# CANTensegrityBoard.net
KiCad netlist of a schematic drawn in EAGLE
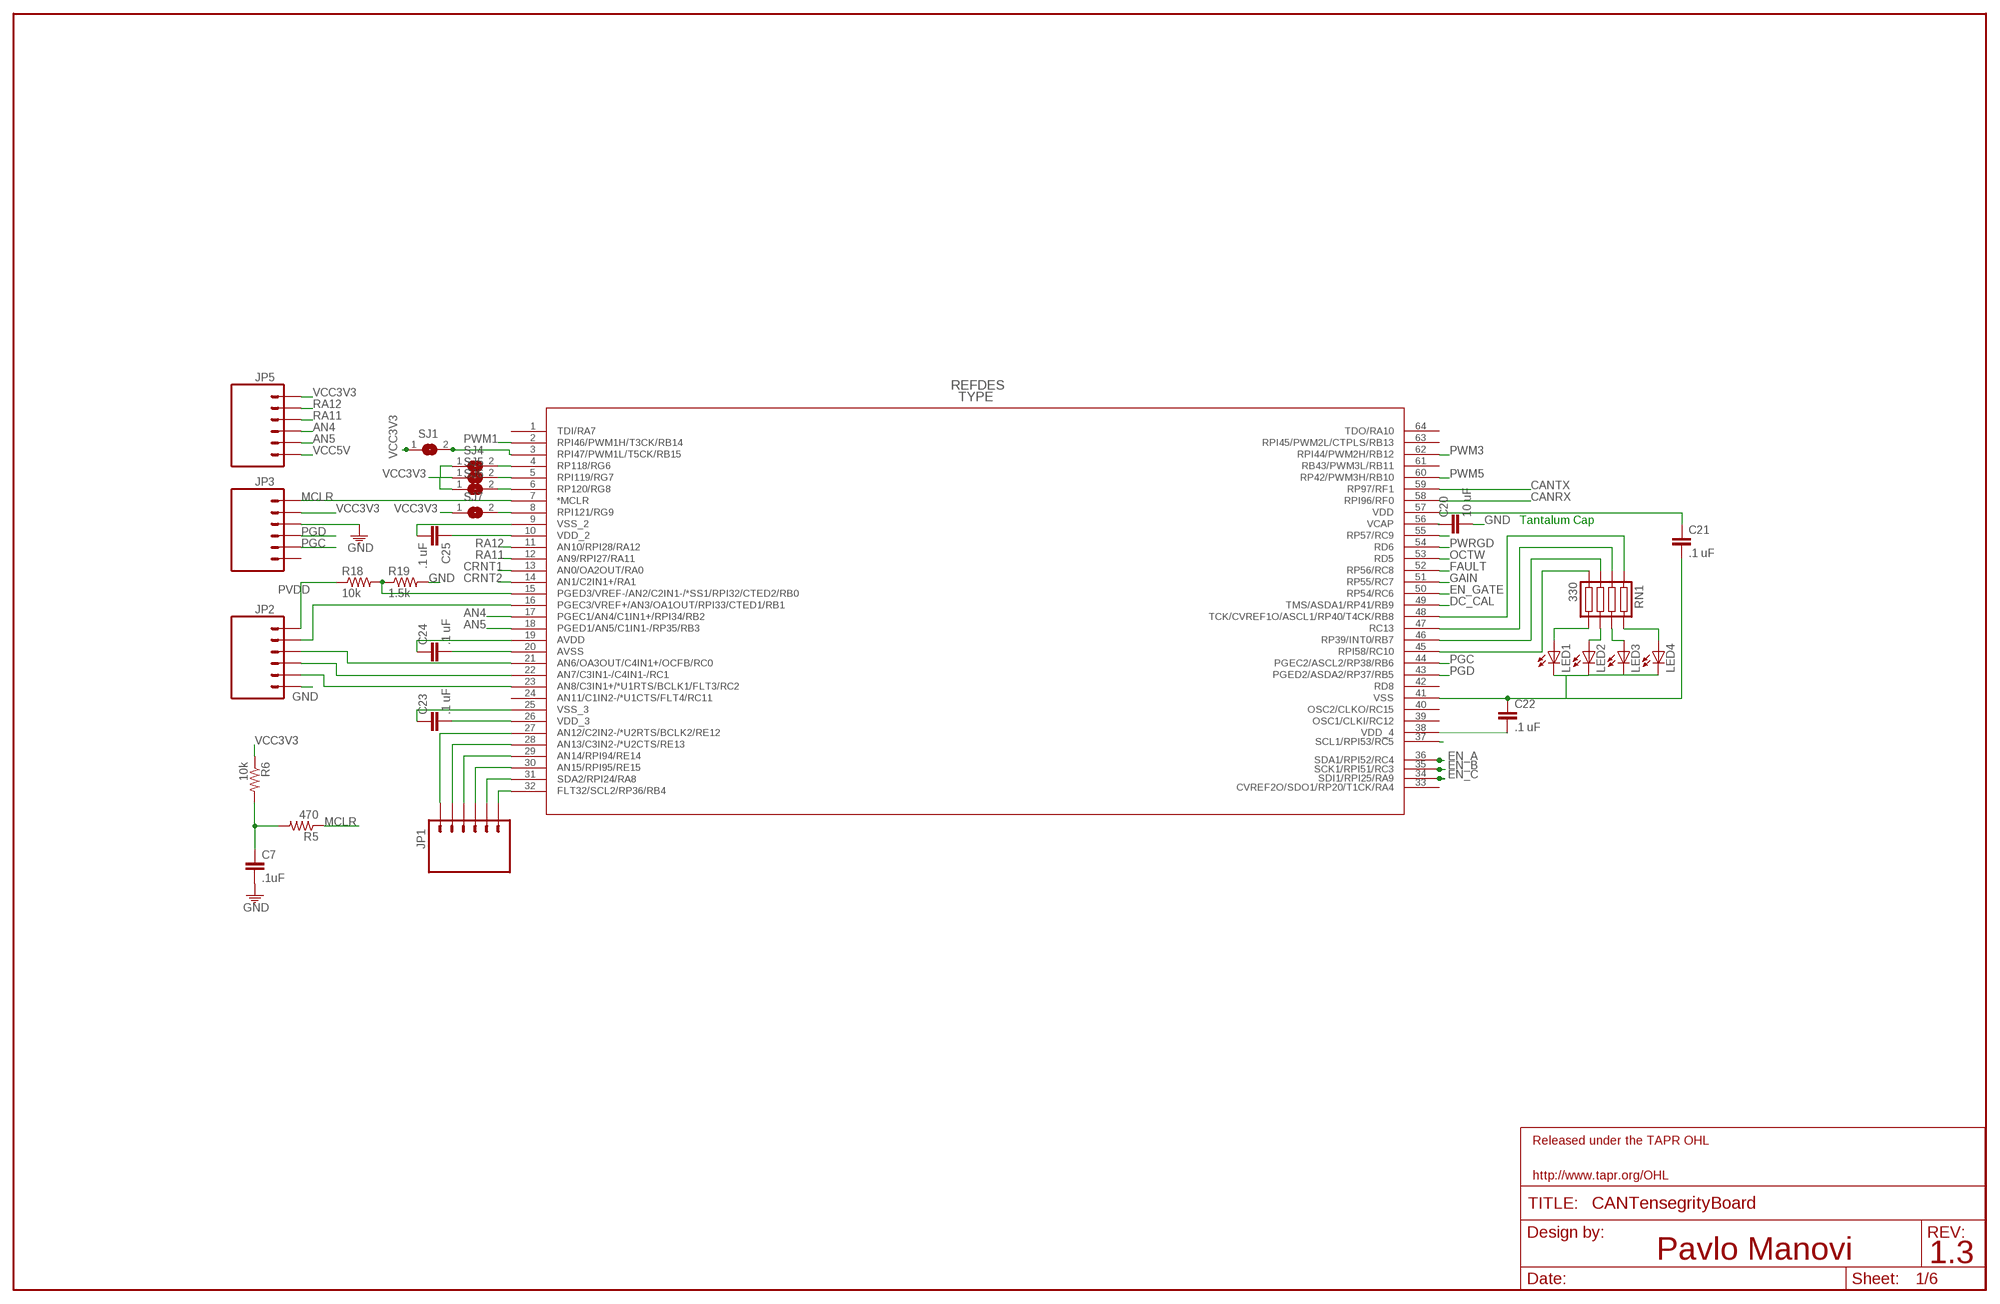
[diagram p0: schematic, sheet 1]
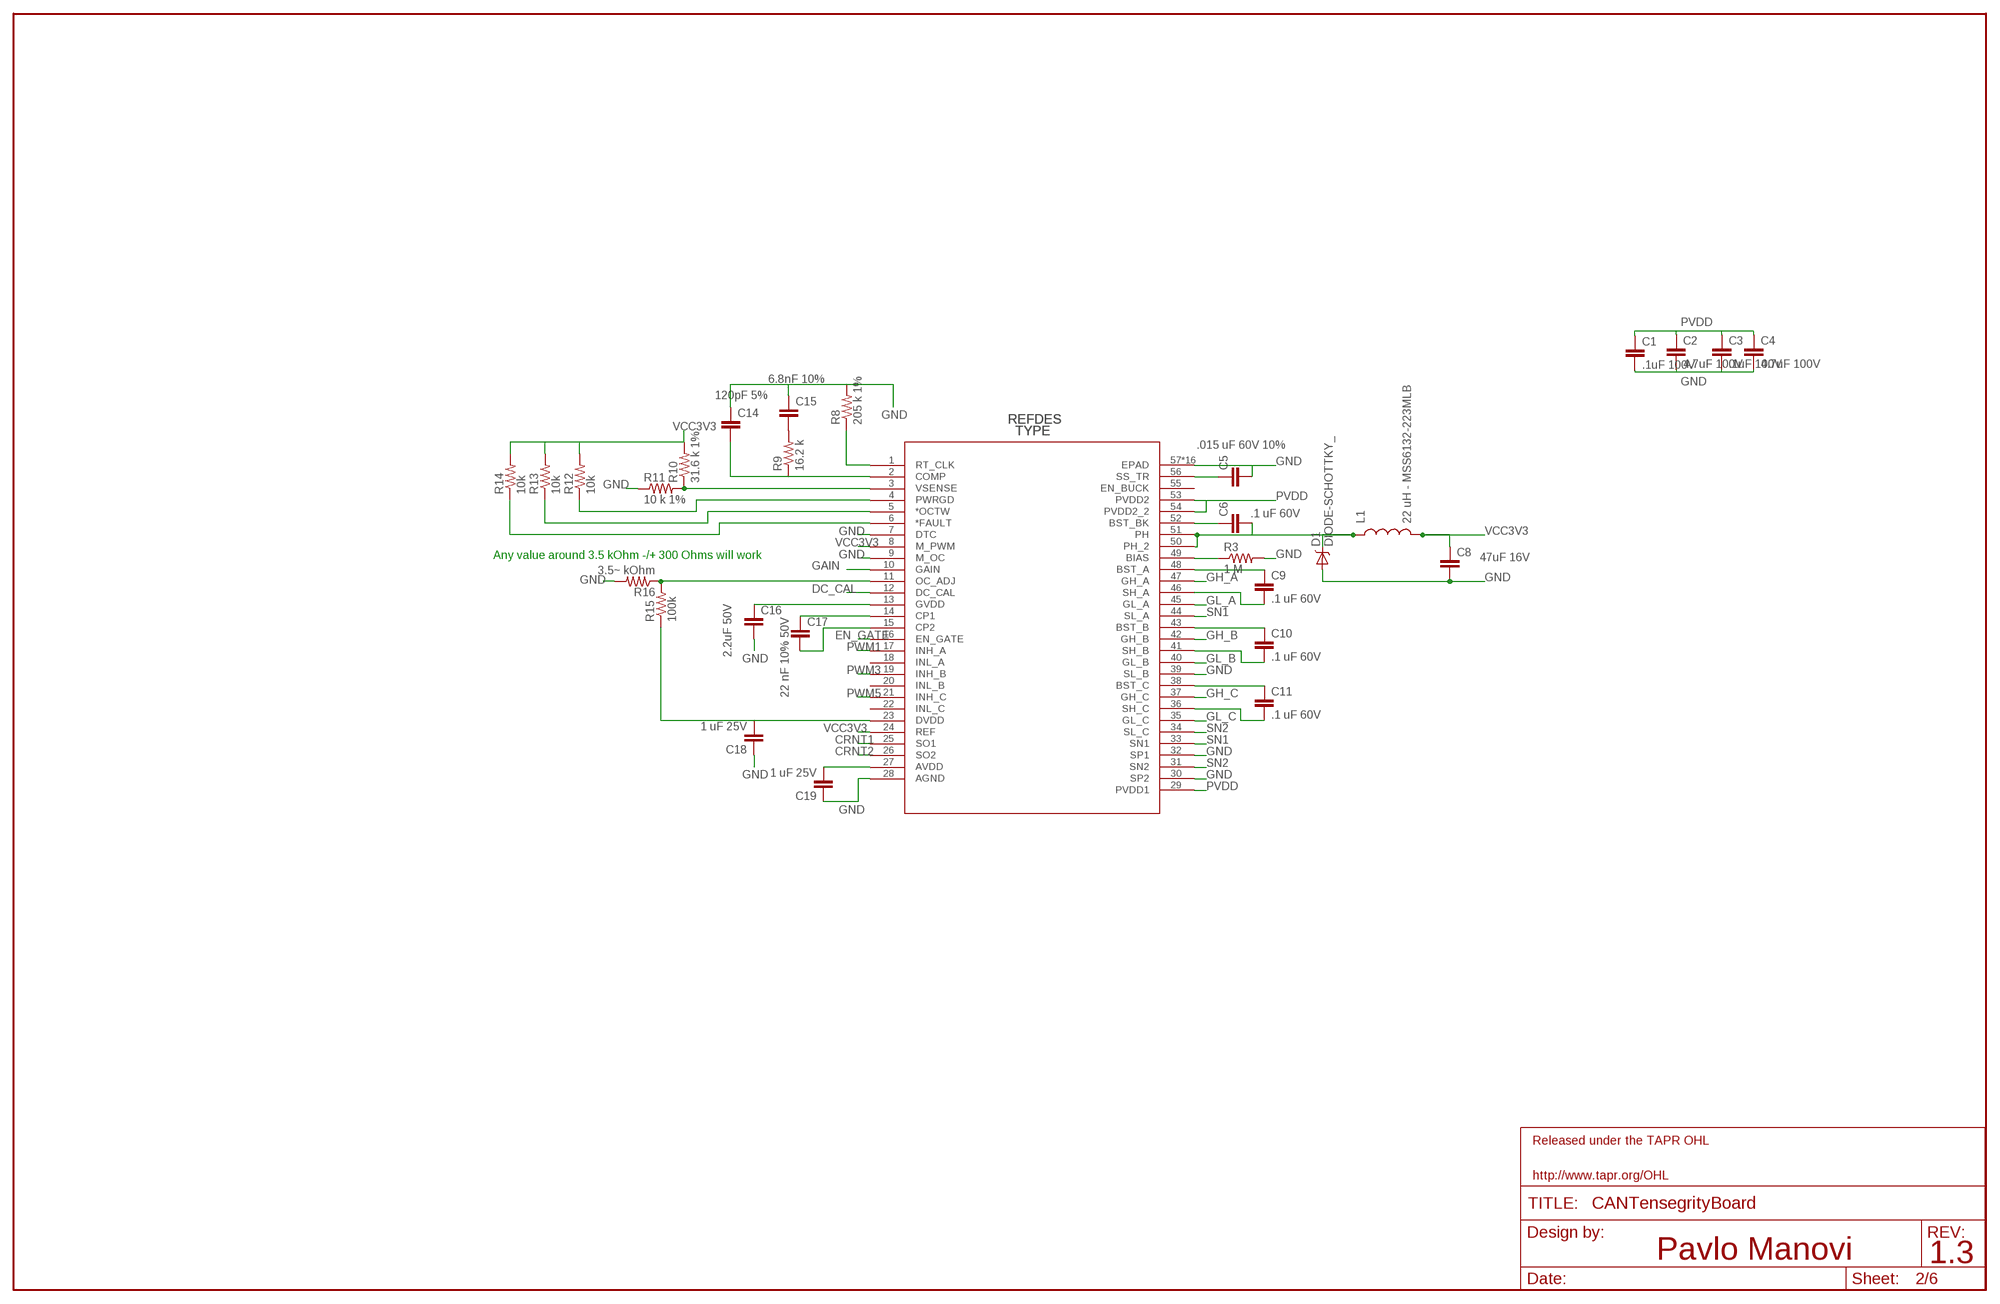
[diagram p1: schematic, sheet 2]
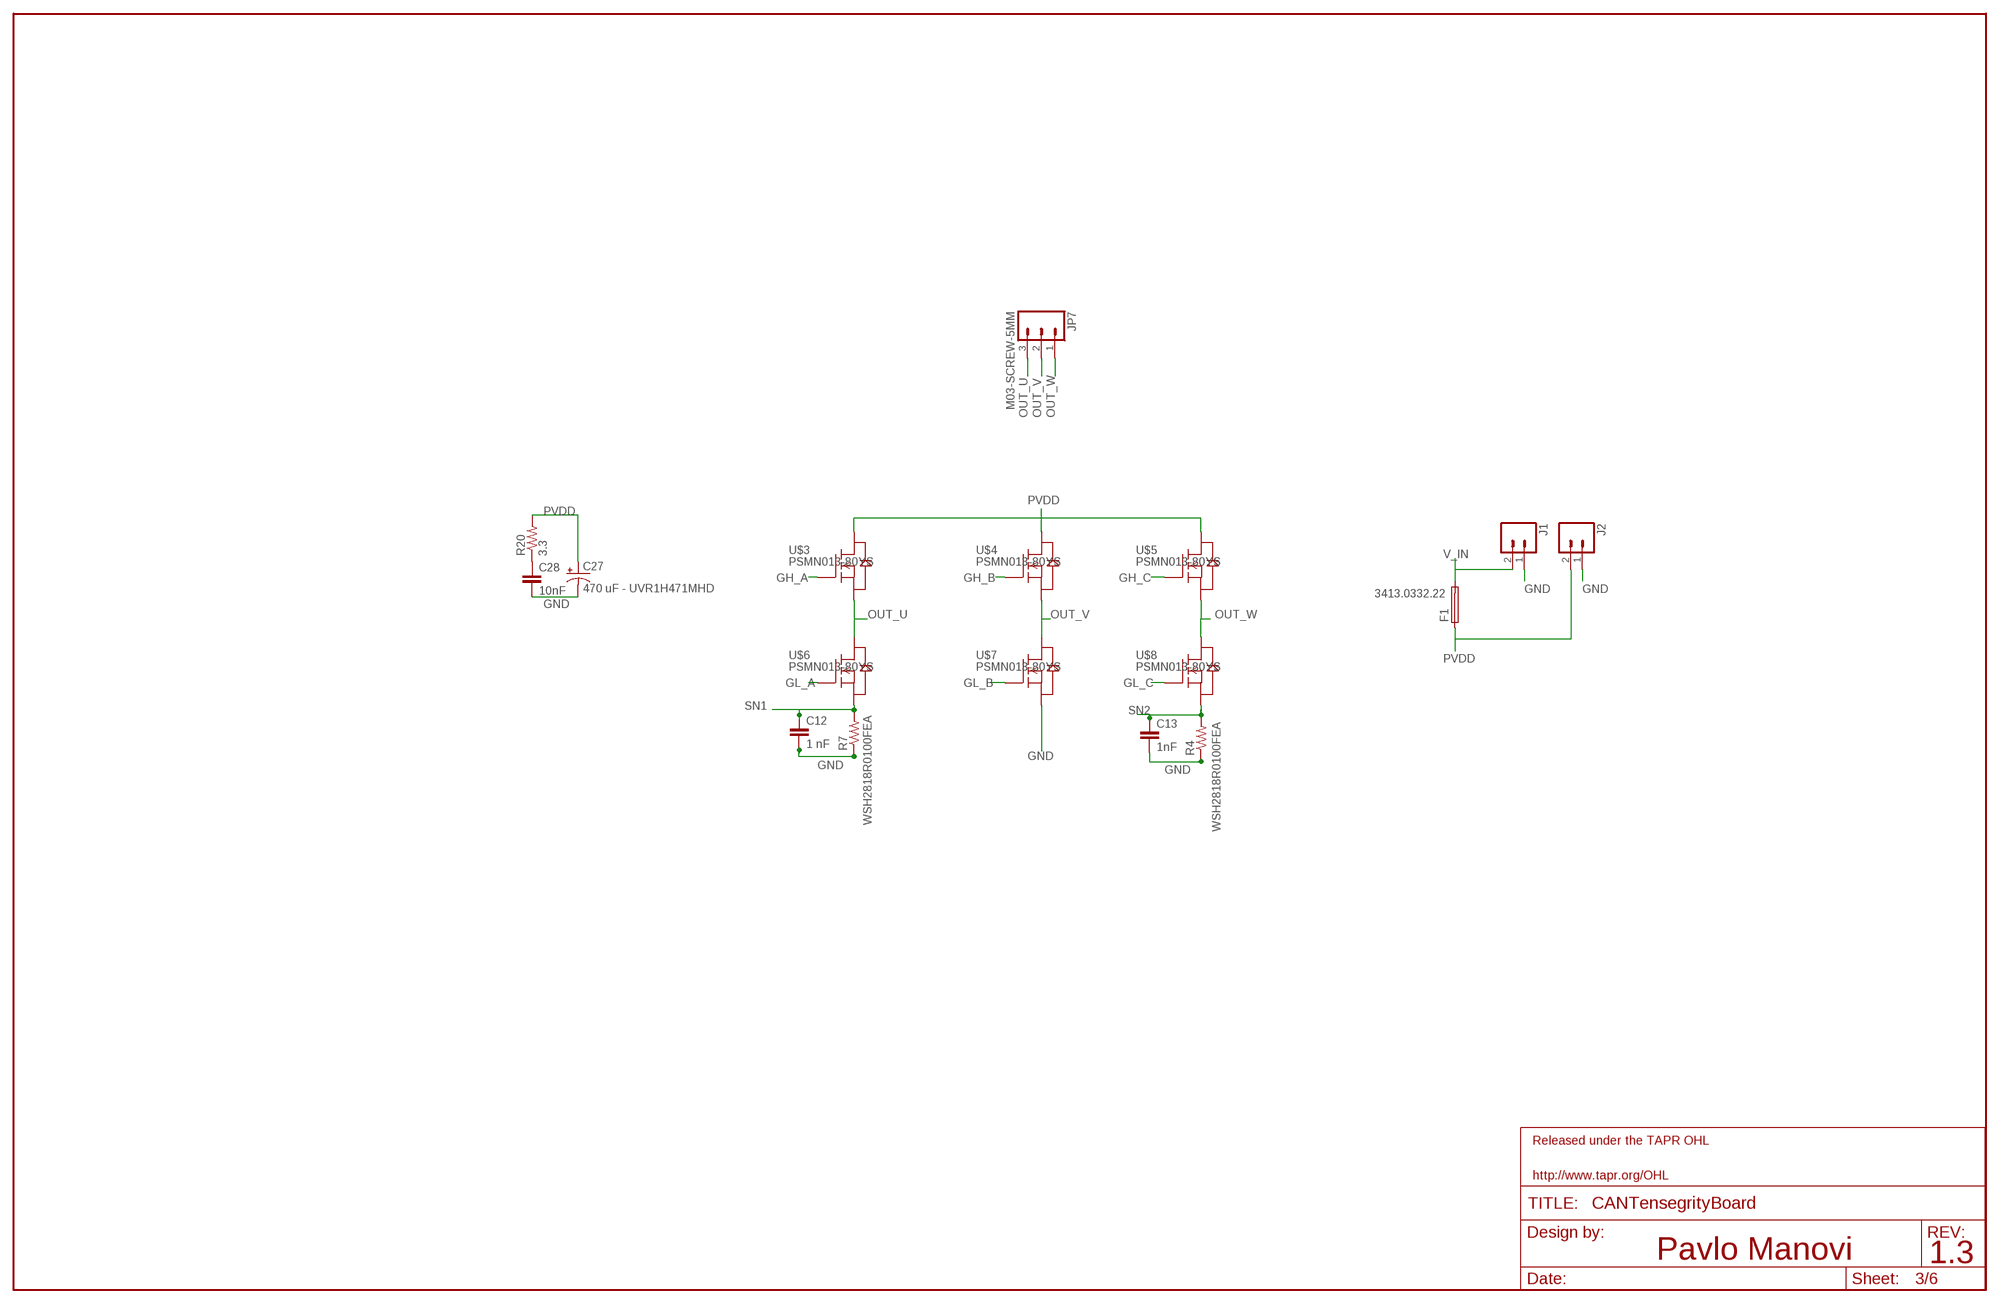
[diagram p2: schematic, sheet 3]
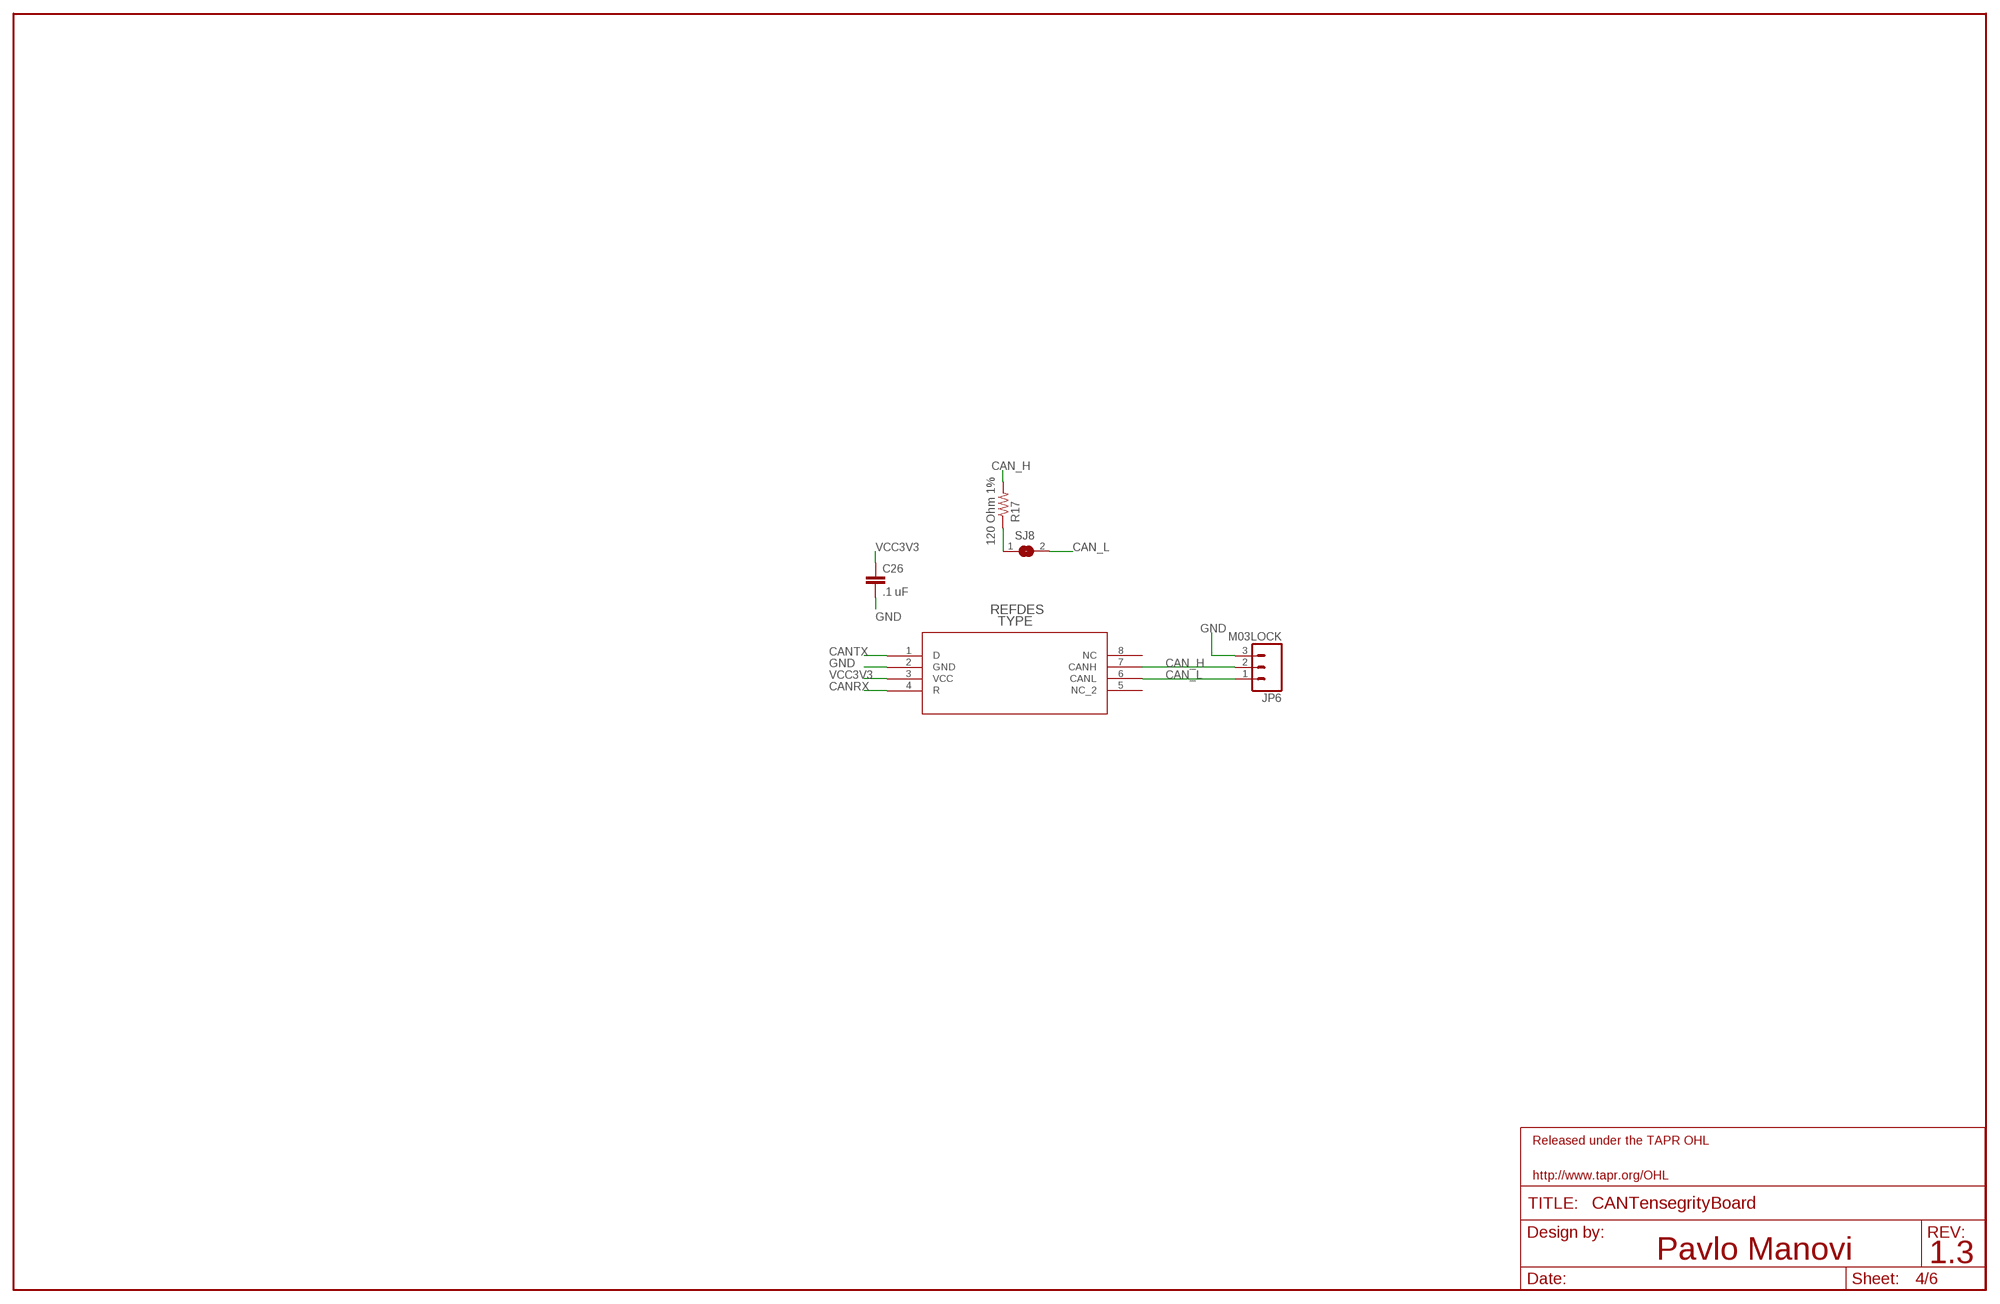
[diagram p3: schematic, sheet 4]
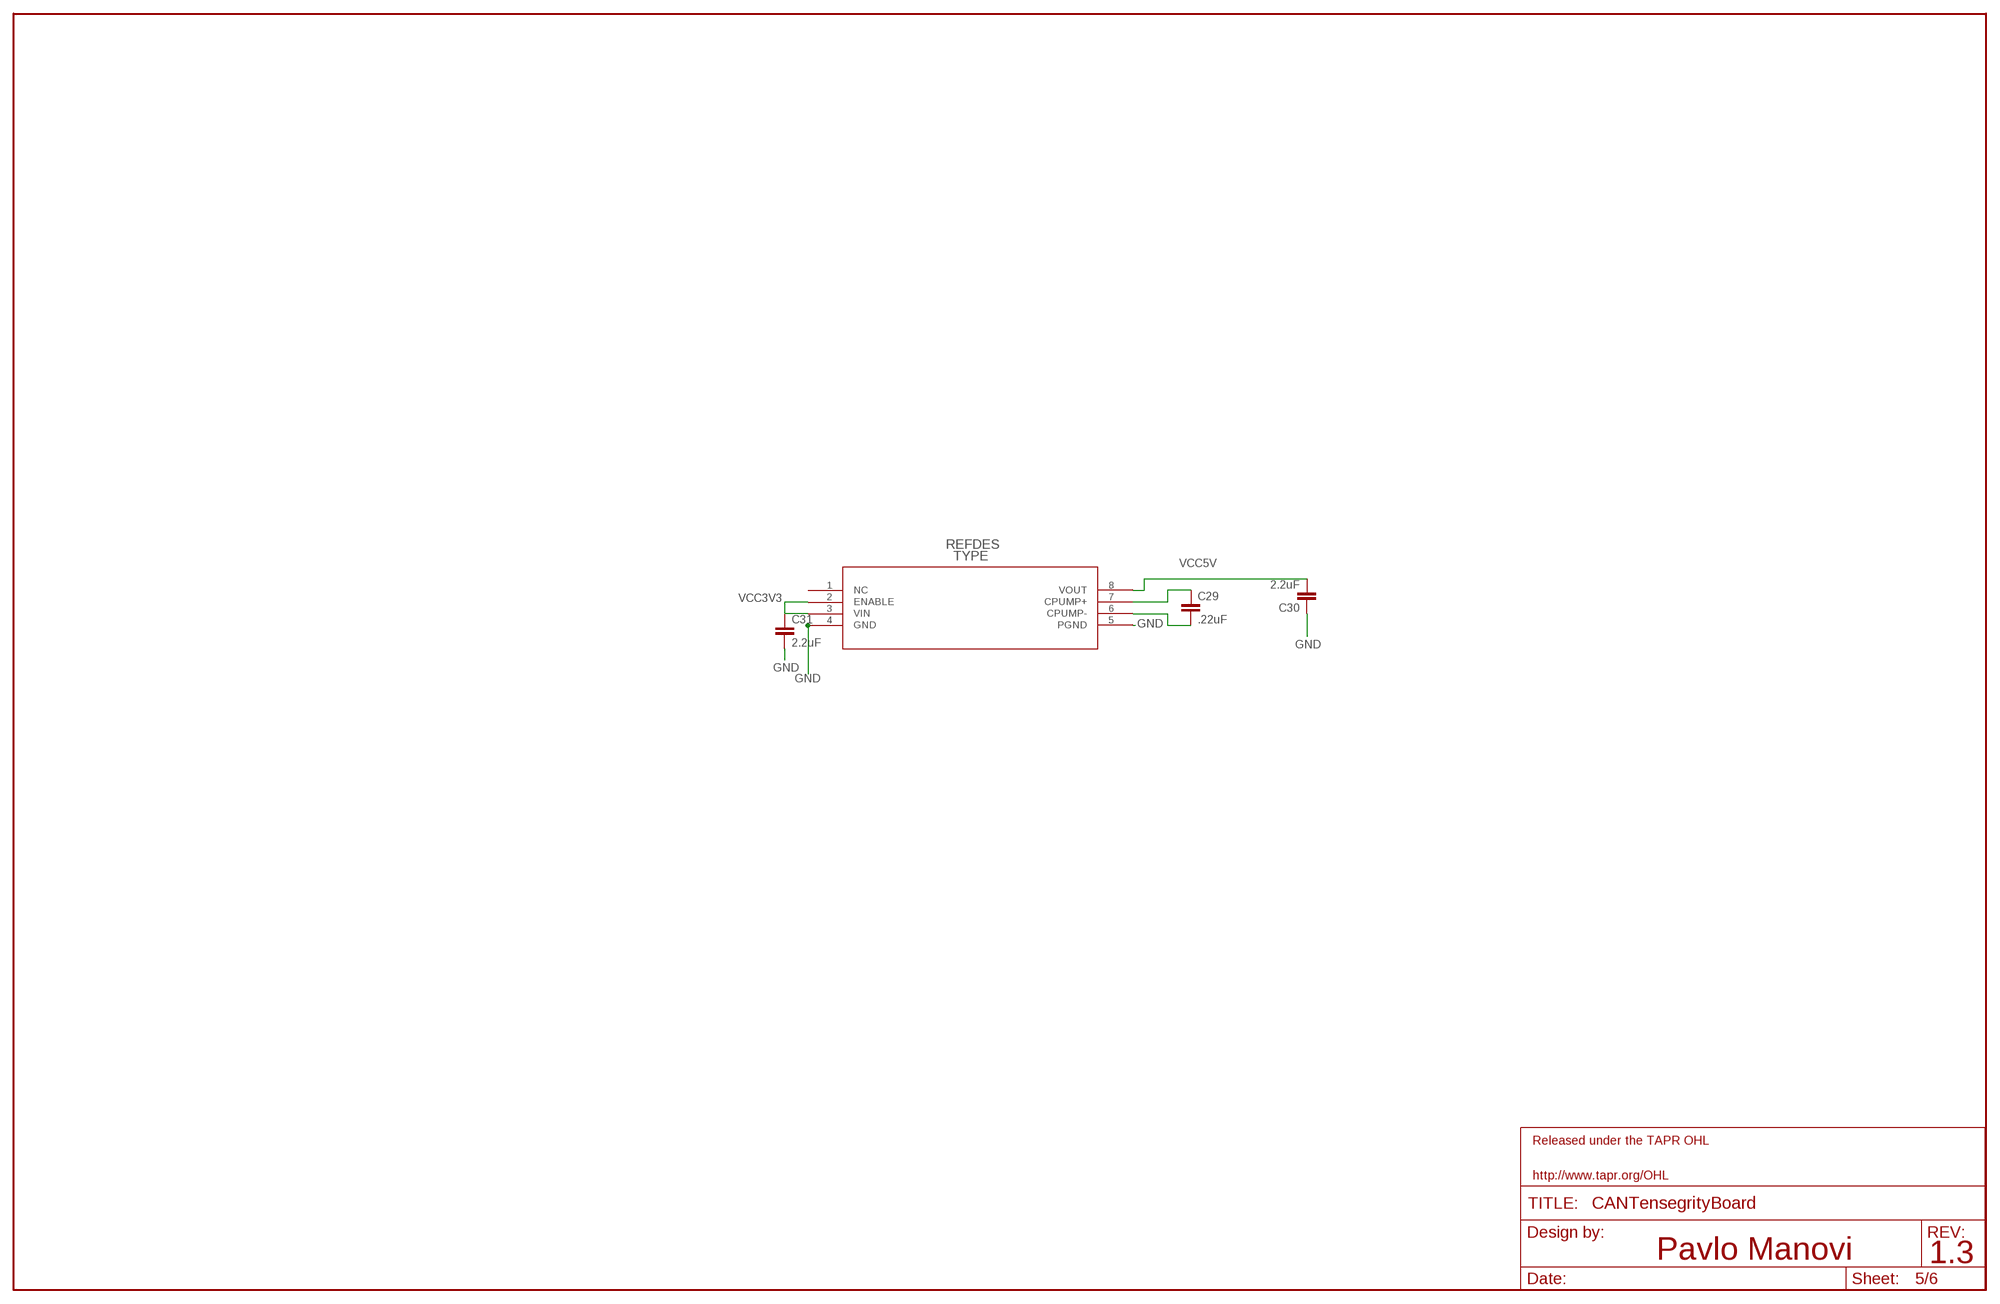
[diagram p4: schematic, sheet 5]
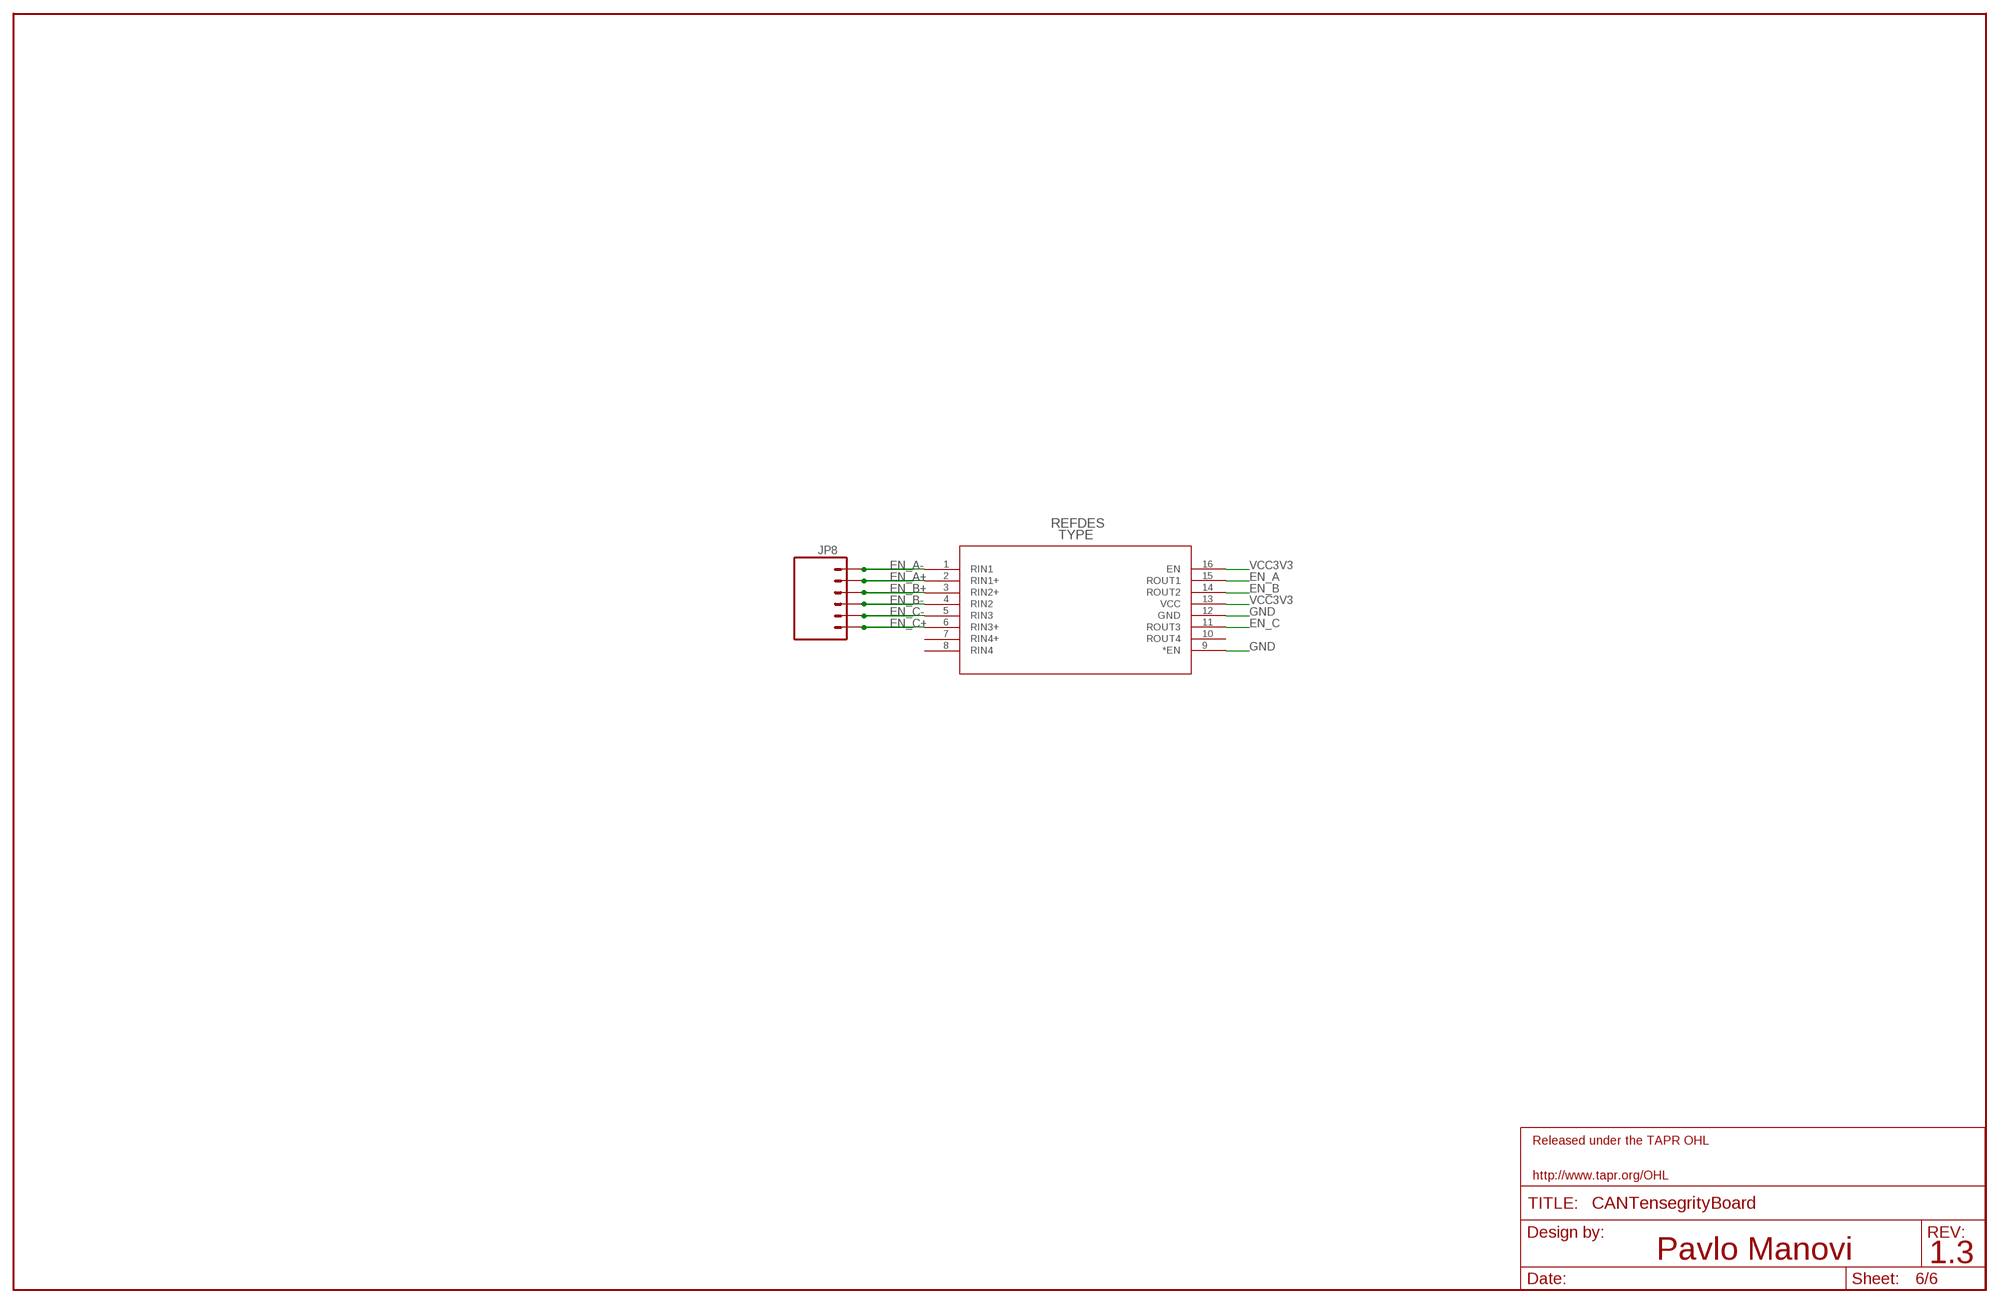
[diagram p5: schematic, sheet 6]

(export (version "E")
  (design (tool "Eeschema 10.0.6"))
  (components
    (comp (ref "C1")
      (value ".1uF 100V")
      (footprint "eagle-import:0805")
      (libsource (lib "eagle-import") (part "CAP0805"))
    )
    (comp (ref "C2")
      (value "4.7uF 100V")
      (footprint "eagle-import:1206")
      (libsource (lib "eagle-import") (part "CAP1206"))
    )
    (comp (ref "C3")
      (value ".1uF 100V")
      (footprint "eagle-import:0805")
      (libsource (lib "eagle-import") (part "CAP0805"))
    )
    (comp (ref "C4")
      (value "4.7uF 100V")
      (footprint "eagle-import:1206")
      (libsource (lib "eagle-import") (part "CAP1206"))
    )
    (comp (ref "C5")
      (value ".015 uF 60V 10%")
      (footprint "eagle-import:0805")
      (libsource (lib "eagle-import") (part "CAP0805"))
    )
    (comp (ref "C6")
      (value ".1 uF 60V")
      (footprint "eagle-import:0805")
      (libsource (lib "eagle-import") (part "CAP0805"))
    )
    (comp (ref "C8")
      (value "47uF 16V")
      (footprint "eagle-import:1206")
      (libsource (lib "eagle-import") (part "CAP1206"))
    )
    (comp (ref "C9")
      (value ".1 uF 60V")
      (footprint "eagle-import:0805")
      (libsource (lib "eagle-import") (part "CAP0805"))
    )
    (comp (ref "C10")
      (value ".1 uF 60V")
      (footprint "eagle-import:0805")
      (libsource (lib "eagle-import") (part "CAP0805"))
    )
    (comp (ref "C11")
      (value ".1 uF 60V")
      (footprint "eagle-import:0805")
      (libsource (lib "eagle-import") (part "CAP0805"))
    )
    (comp (ref "C14")
      (value "120pF 5%")
      (footprint "eagle-import:0805")
      (libsource (lib "eagle-import") (part "CAP0805"))
    )
    (comp (ref "C15")
      (value "6.8nF 10%")
      (footprint "eagle-import:0805")
      (libsource (lib "eagle-import") (part "CAP0805"))
    )
    (comp (ref "C16")
      (value "2.2uF 50V")
      (footprint "eagle-import:1206")
      (libsource (lib "eagle-import") (part "CAP1206"))
    )
    (comp (ref "C17")
      (value "22 nF 10% 50V")
      (footprint "eagle-import:0805")
      (libsource (lib "eagle-import") (part "CAP0805"))
    )
    (comp (ref "C18")
      (value "1 uF 25V")
      (footprint "eagle-import:0805")
      (libsource (lib "eagle-import") (part "CAP0805"))
    )
    (comp (ref "C19")
      (value "1 uF 25V")
      (footprint "eagle-import:0805")
      (libsource (lib "eagle-import") (part "CAP0805"))
    )
    (comp (ref "D1")
      (value "DIODE-SCHOTTKY_")
      (footprint "eagle-import:SMA-DIODE")
      (libsource (lib "eagle-import") (part "DIODE-SCHOTTKY_"))
    )
    (comp (ref "L1")
      (value "22 uH - MSS6132-223MLB")
      (footprint "eagle-import:MSS6132")
      (libsource (lib "eagle-import") (part "INDUCTOR"))
    )
    (comp (ref "R3")
      (value "1 M")
      (footprint "eagle-import:0805")
      (libsource (lib "eagle-import") (part "RESISTOR0805-RES"))
    )
    (comp (ref "R8")
      (value "205 k 1%")
      (footprint "eagle-import:0805")
      (libsource (lib "eagle-import") (part "RESISTOR0805-RES"))
    )
    (comp (ref "R9")
      (value "16.2 k")
      (footprint "eagle-import:0805")
      (libsource (lib "eagle-import") (part "RESISTOR0805-RES"))
    )
    (comp (ref "R10")
      (value "31.6 k 1%")
      (footprint "eagle-import:0805")
      (libsource (lib "eagle-import") (part "RESISTOR0805-RES"))
    )
    (comp (ref "R11")
      (value "10 k 1%")
      (footprint "eagle-import:0805")
      (libsource (lib "eagle-import") (part "RESISTOR0805-RES"))
    )
    (comp (ref "R12")
      (value "10k")
      (footprint "eagle-import:0805")
      (libsource (lib "eagle-import") (part "RESISTOR0805-RES"))
    )
    (comp (ref "R13")
      (value "10k")
      (footprint "eagle-import:0805")
      (libsource (lib "eagle-import") (part "RESISTOR0805-RES"))
    )
    (comp (ref "R14")
      (value "10k")
      (footprint "eagle-import:0805")
      (libsource (lib "eagle-import") (part "RESISTOR0805-RES"))
    )
    (comp (ref "R15")
      (value "100k")
      (footprint "eagle-import:0805")
      (libsource (lib "eagle-import") (part "RESISTOR0805-RES"))
    )
    (comp (ref "R16")
      (value "3.5~ kOhm")
      (footprint "eagle-import:0805")
      (libsource (lib "eagle-import") (part "RESISTOR0805-RES"))
    )
    (comp (ref "U$2")
      (value "DRV8302")
      (footprint "eagle-import:DCA56_6P35X3P600")
      (libsource (lib "eagle-import") (part "DRV8302"))
    )
    (comp (ref "C12")
      (value "1 nF")
      (footprint "eagle-import:0805")
      (libsource (lib "eagle-import") (part "CAP0805"))
    )
    (comp (ref "C13")
      (value "1nF")
      (footprint "eagle-import:0805")
      (libsource (lib "eagle-import") (part "CAP0805"))
    )
    (comp (ref "C27")
      (value "470 uF - UVR1H471MHD")
      (footprint "eagle-import:CPOL-RADIAL-1000UF-25V")
      (libsource (lib "eagle-import") (part "CAP_POLPTH4"))
    )
    (comp (ref "C28")
      (value "10nF")
      (footprint "eagle-import:0805")
      (libsource (lib "eagle-import") (part "CAP0805"))
    )
    (comp (ref "F1")
      (value "3413.0332.22")
      (footprint "eagle-import:LED-1206")
      (libsource (lib "eagle-import") (part "TE5"))
    )
    (comp (ref "J1")
      (value "M02PTH4")
      (footprint "eagle-import:1X02_XTRA_BIG")
      (libsource (lib "eagle-import") (part "M02PTH4"))
    )
    (comp (ref "J2")
      (value "M02PTH4")
      (footprint "eagle-import:1X02_XTRA_BIG")
      (libsource (lib "eagle-import") (part "M02PTH4"))
    )
    (comp (ref "JP7")
      (value "M03-SCREW-5MM")
      (footprint "eagle-import:SCREWTERMINAL-5MM-3")
      (libsource (lib "eagle-import") (part "pavlo_M03-SCREW-5MM"))
    )
    (comp (ref "R4")
      (value "WSH2818R0100FEA")
      (footprint "eagle-import:SMT-REF")
      (libsource (lib "eagle-import") (part "RESISTOR"))
    )
    (comp (ref "R7")
      (value "WSH2818R0100FEA")
      (footprint "eagle-import:SMT-REF")
      (libsource (lib "eagle-import") (part "RESISTOR"))
    )
    (comp (ref "R20")
      (value "3.3")
      (footprint "eagle-import:0805")
      (libsource (lib "eagle-import") (part "RESISTOR0805-RES"))
    )
    (comp (ref "U$3")
      (value "PSMN013-80YS")
      (footprint "eagle-import:TO127P600X120-5N")
      (libsource (lib "eagle-import") (part "PSMN013-80YS"))
    )
    (comp (ref "U$4")
      (value "PSMN013-80YS")
      (footprint "eagle-import:TO127P600X120-5N")
      (libsource (lib "eagle-import") (part "PSMN013-80YS"))
    )
    (comp (ref "U$5")
      (value "PSMN013-80YS")
      (footprint "eagle-import:TO127P600X120-5N")
      (libsource (lib "eagle-import") (part "PSMN013-80YS"))
    )
    (comp (ref "U$6")
      (value "PSMN013-80YS")
      (footprint "eagle-import:TO127P600X120-5N")
      (libsource (lib "eagle-import") (part "PSMN013-80YS"))
    )
    (comp (ref "U$7")
      (value "PSMN013-80YS")
      (footprint "eagle-import:TO127P600X120-5N")
      (libsource (lib "eagle-import") (part "PSMN013-80YS"))
    )
    (comp (ref "U$8")
      (value "PSMN013-80YS")
      (footprint "eagle-import:TO127P600X120-5N")
      (libsource (lib "eagle-import") (part "PSMN013-80YS"))
    )
    (comp (ref "JP8")
      (value "M06SIP_LOCK")
      (footprint "eagle-import:1X06-SIP_LOCK")
      (libsource (lib "eagle-import") (part "M06SIP_LOCK"))
    )
    (comp (ref "U3")
      (value "SN65LVDT348_PW_1")
      (footprint "eagle-import:PW16")
      (libsource (lib "eagle-import") (part "SN65LVDT348_PW_1"))
    )
    (comp (ref "C29")
      (value ".22uF")
      (footprint "eagle-import:0805")
      (libsource (lib "eagle-import") (part "CAP0805"))
    )
    (comp (ref "C30")
      (value "2.2uF")
      (footprint "eagle-import:0805")
      (libsource (lib "eagle-import") (part "CAP0805"))
    )
    (comp (ref "C31")
      (value "2.2uF")
      (footprint "eagle-import:0805")
      (libsource (lib "eagle-import") (part "CAP0805"))
    )
    (comp (ref "U1")
      (value "REG711-5_DGK_8")
      (footprint "eagle-import:DGK8")
      (libsource (lib "eagle-import") (part "REG711-5_DGK_8"))
    )
    (comp (ref "C26")
      (value ".1 uF")
      (footprint "eagle-import:0805")
      (libsource (lib "eagle-import") (part "CAP0805"))
    )
    (comp (ref "JP6")
      (value "M03LOCK")
      (footprint "eagle-import:1X03_LOCK")
      (libsource (lib "eagle-import") (part "M03LOCK"))
    )
    (comp (ref "R17")
      (value "120 Ohm 1%")
      (footprint "eagle-import:0805")
      (libsource (lib "eagle-import") (part "RESISTOR0805-RES"))
    )
    (comp (ref "SJ8") (value "SJ") (footprint "eagle-import:SJ") (libsource (lib "eagle-import") (part "SJ")))
    (comp (ref "U2")
      (value "SN65HVD232_D_8")
      (footprint "eagle-import:D8")
      (libsource (lib "eagle-import") (part "SN65HVD232_D_8"))
    )
    (comp (ref "C7")
      (value ".1uF")
      (footprint "eagle-import:0805")
      (libsource (lib "eagle-import") (part "CAP0805"))
    )
    (comp (ref "C20")
      (value "10 uF")
      (footprint "eagle-import:1206")
      (libsource (lib "eagle-import") (part "CAP1206"))
    )
    (comp (ref "C21")
      (value ".1 uF")
      (footprint "eagle-import:0805")
      (libsource (lib "eagle-import") (part "CAP0805"))
    )
    (comp (ref "C22")
      (value ".1 uF")
      (footprint "eagle-import:0805")
      (libsource (lib "eagle-import") (part "CAP0805"))
    )
    (comp (ref "C23")
      (value ".1 uF")
      (footprint "eagle-import:0805")
      (libsource (lib "eagle-import") (part "CAP0805"))
    )
    (comp (ref "C24")
      (value ".1 uF")
      (footprint "eagle-import:0805")
      (libsource (lib "eagle-import") (part "CAP0805"))
    )
    (comp (ref "C25")
      (value ".1 uF")
      (footprint "eagle-import:0805")
      (libsource (lib "eagle-import") (part "CAP0805"))
    )
    (comp (ref "JP1")
      (value "M06SIP")
      (footprint "eagle-import:1X06")
      (libsource (lib "eagle-import") (part "M06SIP"))
    )
    (comp (ref "JP2")
      (value "M06SIP")
      (footprint "eagle-import:1X06")
      (libsource (lib "eagle-import") (part "M06SIP"))
    )
    (comp (ref "JP3")
      (value "M06LOCK")
      (footprint "eagle-import:1X06_LOCK")
      (libsource (lib "eagle-import") (part "CMPE118lib_M06LOCK"))
    )
    (comp (ref "JP5")
      (value "M06LOCK")
      (footprint "eagle-import:1X06_LOCK")
      (libsource (lib "eagle-import") (part "CMPE118lib_M06LOCK"))
    )
    (comp (ref "LED1")
      (value "LED0805")
      (footprint "eagle-import:LED-0805")
      (libsource (lib "eagle-import") (part "LED0805"))
    )
    (comp (ref "LED2")
      (value "LED0805")
      (footprint "eagle-import:LED-0805")
      (libsource (lib "eagle-import") (part "LED0805"))
    )
    (comp (ref "LED3")
      (value "LED0805")
      (footprint "eagle-import:LED-0805")
      (libsource (lib "eagle-import") (part "LED0805"))
    )
    (comp (ref "LED4")
      (value "LED0805")
      (footprint "eagle-import:LED-0805")
      (libsource (lib "eagle-import") (part "LED0805"))
    )
    (comp (ref "R5")
      (value "470")
      (footprint "eagle-import:0805")
      (libsource (lib "eagle-import") (part "CMPE118lib_RESISTOR0805-RES"))
    )
    (comp (ref "R6")
      (value "10k")
      (footprint "eagle-import:0805")
      (libsource (lib "eagle-import") (part "CMPE118lib_RESISTOR0805-RES"))
    )
    (comp (ref "R18")
      (value "10k")
      (footprint "eagle-import:0805")
      (libsource (lib "eagle-import") (part "RESISTOR0805-RES"))
    )
    (comp (ref "R19")
      (value "1.5k")
      (footprint "eagle-import:0805")
      (libsource (lib "eagle-import") (part "RESISTOR0805-RES"))
    )
    (comp (ref "RN1")
      (value "330")
      (footprint "eagle-import:EXB-38V271JV")
      (libsource (lib "eagle-import") (part "RESISTOR_ARRAY-4"))
    )
    (comp (ref "SJ1") (value "SJ") (footprint "eagle-import:SJ") (libsource (lib "eagle-import") (part "SJ")))
    (comp (ref "SJ4") (value "SJ") (footprint "eagle-import:SJ") (libsource (lib "eagle-import") (part "SJ")))
    (comp (ref "SJ5") (value "SJ") (footprint "eagle-import:SJ") (libsource (lib "eagle-import") (part "SJ")))
    (comp (ref "SJ6") (value "SJ") (footprint "eagle-import:SJ") (libsource (lib "eagle-import") (part "SJ")))
    (comp (ref "SJ7") (value "SJ") (footprint "eagle-import:SJ") (libsource (lib "eagle-import") (part "SJ")))
    (comp (ref "U$1")
      (value "DSPIC33EP128MC502-I/SS")
      (footprint "eagle-import:QFP64-10X10MC")
      (libsource (lib "eagle-import") (part "DSPIC33EP256MC50"))
    )
  )
  (nets
    (net (code "1") (name "AN4") (class "Default")
      (node (ref "JP5") (pin "4") (pinfunction "4_4") (pintype "passive"))
      (node (ref "U$1") (pin "17") (pinfunction "PGEC1/AN4/C1IN1+/RPI34/RB2_17") (pintype "passive"))
    )
    (net (code "2") (name "AN5") (class "Default")
      (node (ref "JP5") (pin "5") (pinfunction "5_5") (pintype "passive"))
      (node (ref "U$1") (pin "18") (pinfunction "PGED1/AN5/C1IN1-/RP35/RB3_18") (pintype "passive"))
    )
    (net (code "3") (name "CANRX") (class "Default")
      (node (ref "U$1") (pin "58") (pinfunction "RPI96/RF0_58") (pintype "passive"))
      (node (ref "U2") (pin "4") (pinfunction "R_4") (pintype "passive"))
    )
    (net (code "4") (name "CANTX") (class "Default")
      (node (ref "U$1") (pin "59") (pinfunction "RP97/RF1_59") (pintype "passive"))
      (node (ref "U2") (pin "1") (pinfunction "D_1") (pintype "passive"))
    )
    (net (code "5") (name "CAN_H") (class "Default")
      (node (ref "JP6") (pin "2") (pinfunction "2_2") (pintype "passive"))
      (node (ref "R17") (pin "2") (pinfunction "2_2") (pintype "passive"))
      (node (ref "U2") (pin "7") (pinfunction "CANH_7") (pintype "passive"))
    )
    (net (code "6") (name "CAN_L") (class "Default")
      (node (ref "JP6") (pin "1") (pinfunction "1_1") (pintype "passive"))
      (node (ref "SJ8") (pin "2") (pinfunction "2_2") (pintype "passive"))
      (node (ref "U2") (pin "6") (pinfunction "CANL_6") (pintype "passive"))
    )
    (net (code "7") (name "CRNT1") (class "Default")
      (node (ref "U$1") (pin "13") (pinfunction "AN0/OA2OUT/RA0_13") (pintype "passive"))
      (node (ref "U$2") (pin "25") (pinfunction "SO1_25") (pintype "passive"))
    )
    (net (code "8") (name "CRNT2") (class "Default")
      (node (ref "U$1") (pin "14") (pinfunction "AN1/C2IN1+/RA1_14") (pintype "passive"))
      (node (ref "U$2") (pin "26") (pinfunction "SO2_26") (pintype "passive"))
    )
    (net (code "9") (name "DC_CAL") (class "Default")
      (node (ref "U$1") (pin "49") (pinfunction "TMS/ASDA1/RP41/RB9_49") (pintype "passive"))
      (node (ref "U$2") (pin "12") (pinfunction "DC_CAL_12") (pintype "passive"))
    )
    (net (code "10") (name "EN_A") (class "Default")
      (node (ref "U$1") (pin "36") (pinfunction "SDA1/RPI52/RC4_36") (pintype "passive"))
      (node (ref "U3") (pin "15") (pinfunction "ROUT1_15") (pintype "passive"))
    )
    (net (code "11") (name "EN_A+") (class "Default")
      (node (ref "JP8") (pin "2") (pinfunction "2_2") (pintype "passive"))
      (node (ref "U3") (pin "2") (pinfunction "RIN1+_2") (pintype "passive"))
    )
    (net (code "12") (name "EN_A-") (class "Default")
      (node (ref "JP8") (pin "1") (pinfunction "1_1") (pintype "passive"))
      (node (ref "U3") (pin "1") (pinfunction "RIN1_1") (pintype "passive"))
    )
    (net (code "13") (name "EN_B") (class "Default")
      (node (ref "U$1") (pin "35") (pinfunction "SCK1/RPI51/RC3_35") (pintype "passive"))
      (node (ref "U3") (pin "14") (pinfunction "ROUT2_14") (pintype "passive"))
    )
    (net (code "14") (name "EN_B+") (class "Default")
      (node (ref "JP8") (pin "3") (pinfunction "3_3") (pintype "passive"))
      (node (ref "U3") (pin "3") (pinfunction "RIN2+_3") (pintype "passive"))
    )
    (net (code "15") (name "EN_B-") (class "Default")
      (node (ref "JP8") (pin "4") (pinfunction "4_4") (pintype "passive"))
      (node (ref "U3") (pin "4") (pinfunction "RIN2_4") (pintype "passive"))
    )
    (net (code "16") (name "EN_C") (class "Default")
      (node (ref "U$1") (pin "34") (pinfunction "SDI1/RPI25/RA9_34") (pintype "passive"))
      (node (ref "U3") (pin "11") (pinfunction "ROUT3_11") (pintype "passive"))
    )
    (net (code "17") (name "EN_C+") (class "Default")
      (node (ref "JP8") (pin "6") (pinfunction "6_6") (pintype "passive"))
      (node (ref "U3") (pin "6") (pinfunction "RIN3+_6") (pintype "passive"))
    )
    (net (code "18") (name "EN_C-") (class "Default")
      (node (ref "JP8") (pin "5") (pinfunction "5_5") (pintype "passive"))
      (node (ref "U3") (pin "5") (pinfunction "RIN3_5") (pintype "passive"))
    )
    (net (code "19") (name "EN_GATE") (class "Default")
      (node (ref "U$1") (pin "50") (pinfunction "RP54/RC6_50") (pintype "passive"))
      (node (ref "U$2") (pin "16") (pinfunction "EN_GATE_16") (pintype "passive"))
    )
    (net (code "20") (name "FAULT") (class "Default")
      (node (ref "R14") (pin "1") (pinfunction "1_1") (pintype "passive"))
      (node (ref "U$1") (pin "52") (pinfunction "RP56/RC8_52") (pintype "passive"))
      (node (ref "U$2") (pin "6") (pinfunction "*FAULT_6") (pintype "passive"))
    )
    (net (code "21") (name "GAIN") (class "Default")
      (node (ref "U$1") (pin "51") (pinfunction "RP55/RC7_51") (pintype "passive"))
      (node (ref "U$2") (pin "10") (pinfunction "GAIN_10") (pintype "passive"))
    )
    (net (code "22") (name "GH_A") (class "Default")
      (node (ref "U$2") (pin "47") (pinfunction "GH_A_47") (pintype "passive"))
      (node (ref "U$3") (pin "4") (pinfunction "G_4") (pintype "passive"))
    )
    (net (code "23") (name "GH_B") (class "Default")
      (node (ref "U$2") (pin "42") (pinfunction "GH_B_42") (pintype "passive"))
      (node (ref "U$4") (pin "4") (pinfunction "G_4") (pintype "passive"))
    )
    (net (code "24") (name "GH_C") (class "Default")
      (node (ref "U$2") (pin "37") (pinfunction "GH_C_37") (pintype "passive"))
      (node (ref "U$5") (pin "4") (pinfunction "G_4") (pintype "passive"))
    )
    (net (code "25") (name "GL_A") (class "Default")
      (node (ref "U$2") (pin "45") (pinfunction "GL_A_45") (pintype "passive"))
      (node (ref "U$6") (pin "4") (pinfunction "G_4") (pintype "passive"))
    )
    (net (code "26") (name "GL_B") (class "Default")
      (node (ref "U$2") (pin "40") (pinfunction "GL_B_40") (pintype "passive"))
      (node (ref "U$7") (pin "4") (pinfunction "G_4") (pintype "passive"))
    )
    (net (code "27") (name "GL_C") (class "Default")
      (node (ref "U$2") (pin "35") (pinfunction "GL_C_35") (pintype "passive"))
      (node (ref "U$8") (pin "4") (pinfunction "G_4") (pintype "passive"))
    )
    (net (code "28") (name "GND") (class "Default")
      (node (ref "C1") (pin "2") (pinfunction "2_2") (pintype "passive"))
      (node (ref "C12") (pin "2") (pinfunction "2_2") (pintype "passive"))
      (node (ref "C13") (pin "2") (pinfunction "2_2") (pintype "passive"))
      (node (ref "C14") (pin "1") (pinfunction "1_1") (pintype "passive"))
      (node (ref "C15") (pin "1") (pinfunction "1_1") (pintype "passive"))
      (node (ref "C16") (pin "2") (pinfunction "2_2") (pintype "passive"))
      (node (ref "C18") (pin "1") (pinfunction "1_1") (pintype "passive"))
      (node (ref "C19") (pin "1") (pinfunction "1_1") (pintype "passive"))
      (node (ref "C2") (pin "2") (pinfunction "2_2") (pintype "passive"))
      (node (ref "C20") (pin "2") (pinfunction "2_2") (pintype "passive"))
      (node (ref "C21") (pin "2") (pinfunction "2_2") (pintype "passive"))
      (node (ref "C22") (pin "1") (pinfunction "1_1") (pintype "passive"))
      (node (ref "C23") (pin "1") (pinfunction "1_1") (pintype "passive"))
      (node (ref "C24") (pin "2") (pinfunction "2_2") (pintype "passive"))
      (node (ref "C25") (pin "2") (pinfunction "2_2") (pintype "passive"))
      (node (ref "C26") (pin "2") (pinfunction "2_2") (pintype "passive"))
      (node (ref "C27") (pin "2") (pinfunction "-_2") (pintype "passive"))
      (node (ref "C28") (pin "2") (pinfunction "2_2") (pintype "passive"))
      (node (ref "C3") (pin "2") (pinfunction "2_2") (pintype "passive"))
      (node (ref "C30") (pin "1") (pinfunction "1_1") (pintype "passive"))
      (node (ref "C31") (pin "2") (pinfunction "2_2") (pintype "passive"))
      (node (ref "C4") (pin "2") (pinfunction "2_2") (pintype "passive"))
      (node (ref "C5") (pin "2") (pinfunction "2_2") (pintype "passive"))
      (node (ref "C7") (pin "2") (pinfunction "2_2") (pintype "passive"))
      (node (ref "C8") (pin "2") (pinfunction "2_2") (pintype "passive"))
      (node (ref "D1") (pin "A") (pinfunction "A_A") (pintype "passive"))
      (node (ref "J1") (pin "1") (pinfunction "2_1") (pintype "passive"))
      (node (ref "J2") (pin "1") (pinfunction "2_1") (pintype "passive"))
      (node (ref "JP2") (pin "6") (pinfunction "6_6") (pintype "passive"))
      (node (ref "JP3") (pin "3") (pinfunction "3_3") (pintype "passive"))
      (node (ref "JP6") (pin "3") (pinfunction "3_3") (pintype "passive"))
      (node (ref "LED1") (pin "2") (pinfunction "C_2") (pintype "passive"))
      (node (ref "LED2") (pin "2") (pinfunction "C_2") (pintype "passive"))
      (node (ref "LED3") (pin "2") (pinfunction "C_2") (pintype "passive"))
      (node (ref "LED4") (pin "2") (pinfunction "C_2") (pintype "passive"))
      (node (ref "R11") (pin "1") (pinfunction "1_1") (pintype "passive"))
      (node (ref "R16") (pin "2") (pinfunction "2_2") (pintype "passive"))
      (node (ref "R19") (pin "2") (pinfunction "2_2") (pintype "passive"))
      (node (ref "R3") (pin "2") (pinfunction "2_2") (pintype "passive"))
      (node (ref "R4") (pin "1") (pinfunction "1_1") (pintype "passive"))
      (node (ref "R7") (pin "1") (pinfunction "1_1") (pintype "passive"))
      (node (ref "R8") (pin "2") (pinfunction "2_2") (pintype "passive"))
      (node (ref "U$1") (pin "20") (pinfunction "AVSS_20") (pintype "passive"))
      (node (ref "U$1") (pin "25") (pinfunction "VSS_3_25") (pintype "passive"))
      (node (ref "U$1") (pin "41") (pinfunction "VSS_41") (pintype "passive"))
      (node (ref "U$1") (pin "9") (pinfunction "VSS_2_9") (pintype "passive"))
      (node (ref "U$2") (pin "28") (pinfunction "AGND_28") (pintype "passive"))
      (node (ref "U$2") (pin "30") (pinfunction "SP2_30") (pintype "passive"))
      (node (ref "U$2") (pin "32") (pinfunction "SP1_32") (pintype "passive"))
      (node (ref "U$2") (pin "39") (pinfunction "SL_B_39") (pintype "passive"))
      (node (ref "U$2") (pin "57") (pinfunction "EPAD_57") (pintype "passive"))
      (node (ref "U$2") (pin "7") (pinfunction "DTC_7") (pintype "passive"))
      (node (ref "U$2") (pin "9") (pinfunction "M_OC_9") (pintype "passive"))
      (node (ref "U$2") (pin "P$1") (pinfunction "EPAD_P$1") (pintype "passive"))
      (node (ref "U$2") (pin "P$10") (pinfunction "EPAD_P$10") (pintype "passive"))
      (node (ref "U$2") (pin "P$11") (pinfunction "EPAD_P$11") (pintype "passive"))
      (node (ref "U$2") (pin "P$12") (pinfunction "EPAD_P$12") (pintype "passive"))
      (node (ref "U$2") (pin "P$13") (pinfunction "EPAD_P$13") (pintype "passive"))
      (node (ref "U$2") (pin "P$14") (pinfunction "EPAD_P$14") (pintype "passive"))
      (node (ref "U$2") (pin "P$15") (pinfunction "EPAD_P$15") (pintype "passive"))
      (node (ref "U$2") (pin "P$2") (pinfunction "EPAD_P$2") (pintype "passive"))
      (node (ref "U$2") (pin "P$3") (pinfunction "EPAD_P$3") (pintype "passive"))
      (node (ref "U$2") (pin "P$4") (pinfunction "EPAD_P$4") (pintype "passive"))
      (node (ref "U$2") (pin "P$5") (pinfunction "EPAD_P$5") (pintype "passive"))
      (node (ref "U$2") (pin "P$6") (pinfunction "EPAD_P$6") (pintype "passive"))
      (node (ref "U$2") (pin "P$7") (pinfunction "EPAD_P$7") (pintype "passive"))
      (node (ref "U$2") (pin "P$8") (pinfunction "EPAD_P$8") (pintype "passive"))
      (node (ref "U$2") (pin "P$9") (pinfunction "EPAD_P$9") (pintype "passive"))
      (node (ref "U$7") (pin "1") (pinfunction "S_1") (pintype "passive"))
      (node (ref "U$7") (pin "2") (pinfunction "S_2") (pintype "passive"))
      (node (ref "U$7") (pin "3") (pinfunction "S_3") (pintype "passive"))
      (node (ref "U1") (pin "4") (pinfunction "GND_4") (pintype "passive"))
      (node (ref "U1") (pin "5") (pinfunction "PGND_5") (pintype "passive"))
      (node (ref "U2") (pin "2") (pinfunction "GND_2") (pintype "passive"))
      (node (ref "U3") (pin "12") (pinfunction "GND_12") (pintype "passive"))
      (node (ref "U3") (pin "9") (pinfunction "*EN_9") (pintype "passive"))
    )
    (net (code "29") (name "MCLR") (class "Default")
      (node (ref "JP3") (pin "1") (pinfunction "1_1") (pintype "passive"))
      (node (ref "R5") (pin "1") (pinfunction "1_1") (pintype "passive"))
      (node (ref "U$1") (pin "7") (pinfunction "*MCLR_7") (pintype "passive"))
    )
    (net (code "30") (name "Net-(C7-Pad1)") (class "Default")
      (node (ref "C7") (pin "1") (pinfunction "1_1") (pintype "passive"))
      (node (ref "R5") (pin "2") (pinfunction "2_2") (pintype "passive"))
      (node (ref "R6") (pin "2") (pinfunction "2_2") (pintype "passive"))
    )
    (net (code "31") (name "Net-(C15-Pad2)") (class "Default")
      (node (ref "C15") (pin "2") (pinfunction "2_2") (pintype "passive"))
      (node (ref "R9") (pin "2") (pinfunction "2_2") (pintype "passive"))
    )
    (net (code "32") (name "Net-(C28-Pad1)") (class "Default")
      (node (ref "C28") (pin "1") (pinfunction "1_1") (pintype "passive"))
      (node (ref "R20") (pin "1") (pinfunction "1_1") (pintype "passive"))
    )
    (net (code "33") (name "Net-(L1-1)") (class "Default")
      (node (ref "C6") (pin "2") (pinfunction "2_2") (pintype "passive"))
      (node (ref "D1") (pin "C") (pinfunction "C_C") (pintype "passive"))
      (node (ref "L1") (pin "P$1") (pinfunction "1_P$1") (pintype "passive"))
      (node (ref "U$2") (pin "51") (pinfunction "PH_51") (pintype "passive"))
    )
    (net (code "34") (name "Net-(LED1-A)") (class "Default")
      (node (ref "LED1") (pin "1") (pinfunction "A_1") (pintype "passive"))
      (node (ref "RN1") (pin "P$5") (pinfunction "5_P$5") (pintype "passive"))
    )
    (net (code "35") (name "Net-(LED2-A)") (class "Default")
      (node (ref "LED2") (pin "1") (pinfunction "A_1") (pintype "passive"))
      (node (ref "RN1") (pin "P$6") (pinfunction "6_P$6") (pintype "passive"))
    )
    (net (code "36") (name "Net-(LED3-A)") (class "Default")
      (node (ref "LED3") (pin "1") (pinfunction "A_1") (pintype "passive"))
      (node (ref "RN1") (pin "P$7") (pinfunction "7_P$7") (pintype "passive"))
    )
    (net (code "37") (name "Net-(LED4-A)") (class "Default")
      (node (ref "LED4") (pin "1") (pinfunction "A_1") (pintype "passive"))
      (node (ref "RN1") (pin "P$8") (pinfunction "8_P$8") (pintype "passive"))
    )
    (net (code "38") (name "Net-(R17-Pad1)") (class "Default")
      (node (ref "R17") (pin "1") (pinfunction "1_1") (pintype "passive"))
      (node (ref "SJ8") (pin "1") (pinfunction "1_1") (pintype "passive"))
    )
    (net (code "39") (name "Net-(RN1-1)") (class "Default")
      (node (ref "RN1") (pin "P$1") (pinfunction "1_P$1") (pintype "passive"))
      (node (ref "U$1") (pin "48") (pinfunction "TCK/CVREF1O/ASCL1/RP40/T4CK/RB8_48") (pintype "passive"))
    )
    (net (code "40") (name "Net-(RN1-2)") (class "Default")
      (node (ref "RN1") (pin "P$2") (pinfunction "2_P$2") (pintype "passive"))
      (node (ref "U$1") (pin "47") (pinfunction "RC13_47") (pintype "passive"))
    )
    (net (code "41") (name "Net-(RN1-3)") (class "Default")
      (node (ref "RN1") (pin "P$3") (pinfunction "3_P$3") (pintype "passive"))
      (node (ref "U$1") (pin "46") (pinfunction "RP39/INT0/RB7_46") (pintype "passive"))
    )
    (net (code "42") (name "Net-(RN1-4)") (class "Default")
      (node (ref "RN1") (pin "P$4") (pinfunction "4_P$4") (pintype "passive"))
      (node (ref "U$1") (pin "45") (pinfunction "RPI58/RC10_45") (pintype "passive"))
    )
    (net (code "43") (name "Net-(U$1-AN6{slash}OA3OUT{slash}C4IN1+{slash}OCFB{slash}RC0)") (class "Default")
      (node (ref "JP2") (pin "3") (pinfunction "3_3") (pintype "passive"))
      (node (ref "U$1") (pin "21") (pinfunction "AN6/OA3OUT/C4IN1+/OCFB/RC0_21") (pintype "passive"))
    )
    (net (code "44") (name "Net-(U$1-AN7{slash}C3IN1-{slash}C4IN1-{slash}RC1)") (class "Default")
      (node (ref "JP2") (pin "4") (pinfunction "4_4") (pintype "passive"))
      (node (ref "U$1") (pin "22") (pinfunction "AN7/C3IN1-/C4IN1-/RC1_22") (pintype "passive"))
    )
    (net (code "45") (name "Net-(U$1-AN8{slash}C3IN1+{slash}*U1RTS{slash}BCLK1{slash}FLT3{slash}RC2)") (class "Default")
      (node (ref "JP2") (pin "5") (pinfunction "5_5") (pintype "passive"))
      (node (ref "U$1") (pin "23") (pinfunction "AN8/C3IN1+/*U1RTS/BCLK1/FLT3/RC2_23") (pintype "passive"))
    )
    (net (code "46") (name "Net-(U$1-AN12{slash}C2IN2-{slash}*U2RTS{slash}BCLK2{slash}RE12)") (class "Default")
      (node (ref "JP1") (pin "1") (pinfunction "1_1") (pintype "passive"))
      (node (ref "U$1") (pin "27") (pinfunction "AN12/C2IN2-/*U2RTS/BCLK2/RE12_27") (pintype "passive"))
    )
    (net (code "47") (name "Net-(U$1-AN13{slash}C3IN2-{slash}*U2CTS{slash}RE13)") (class "Default")
      (node (ref "JP1") (pin "2") (pinfunction "2_2") (pintype "passive"))
      (node (ref "U$1") (pin "28") (pinfunction "AN13/C3IN2-/*U2CTS/RE13_28") (pintype "passive"))
    )
    (net (code "48") (name "Net-(U$1-AN14{slash}RPI94{slash}RE14)") (class "Default")
      (node (ref "JP1") (pin "3") (pinfunction "3_3") (pintype "passive"))
      (node (ref "U$1") (pin "29") (pinfunction "AN14/RPI94/RE14_29") (pintype "passive"))
    )
    (net (code "49") (name "Net-(U$1-AN15{slash}RPI95{slash}RE15)") (class "Default")
      (node (ref "JP1") (pin "4") (pinfunction "4_4") (pintype "passive"))
      (node (ref "U$1") (pin "30") (pinfunction "AN15/RPI95/RE15_30") (pintype "passive"))
    )
    (net (code "50") (name "Net-(U$1-FLT32{slash}SCL2{slash}RP36{slash}RB4)") (class "Default")
      (node (ref "JP1") (pin "6") (pinfunction "6_6") (pintype "passive"))
      (node (ref "U$1") (pin "32") (pinfunction "FLT32/SCL2/RP36/RB4_32") (pintype "passive"))
    )
    (net (code "51") (name "Net-(U$1-PGEC3{slash}VREF+{slash}AN3{slash}OA1OUT{slash}RPI33{slash}CTED1{slash}RB1)") (class "Default")
      (node (ref "JP2") (pin "2") (pinfunction "2_2") (pintype "passive"))
      (node (ref "U$1") (pin "16") (pinfunction "PGEC3/VREF+/AN3/OA1OUT/RPI33/CTED1/RB1_16") (pintype "passive"))
    )
    (net (code "52") (name "Net-(U$1-PGED3{slash}VREF-{slash}AN2{slash}C2IN1-{slash}*SS1{slash}RPI32{slash}CTED2{slash}RB0)") (class "Default")
      (node (ref "R18") (pin "2") (pinfunction "2_2") (pintype "passive"))
      (node (ref "R19") (pin "1") (pinfunction "1_1") (pintype "passive"))
      (node (ref "U$1") (pin "15") (pinfunction "PGED3/VREF-/AN2/C2IN1-/*SS1/RPI32/CTED2/RB0_15") (pintype "passive"))
    )
    (net (code "53") (name "Net-(U$1-RP118{slash}RG6)") (class "Default")
      (node (ref "SJ4") (pin "2") (pinfunction "2_2") (pintype "passive"))
      (node (ref "U$1") (pin "4") (pinfunction "RP118/RG6_4") (pintype "passive"))
    )
    (net (code "54") (name "Net-(U$1-RP120{slash}RG8)") (class "Default")
      (node (ref "SJ6") (pin "2") (pinfunction "2_2") (pintype "passive"))
      (node (ref "U$1") (pin "6") (pinfunction "RP120/RG8_6") (pintype "passive"))
    )
    (net (code "55") (name "Net-(U$1-RPI47{slash}PWM1L{slash}T5CK{slash}RB15)") (class "Default")
      (node (ref "SJ1") (pin "2") (pinfunction "2_2") (pintype "passive"))
      (node (ref "U$1") (pin "3") (pinfunction "RPI47/PWM1L/T5CK/RB15_3") (pintype "passive"))
    )
    (net (code "56") (name "Net-(U$1-RPI119{slash}RG7)") (class "Default")
      (node (ref "SJ5") (pin "2") (pinfunction "2_2") (pintype "passive"))
      (node (ref "U$1") (pin "5") (pinfunction "RPI119/RG7_5") (pintype "passive"))
    )
    (net (code "57") (name "Net-(U$1-RPI121{slash}RG9)") (class "Default")
      (node (ref "SJ7") (pin "2") (pinfunction "2_2") (pintype "passive"))
      (node (ref "U$1") (pin "8") (pinfunction "RPI121/RG9_8") (pintype "passive"))
    )
    (net (code "58") (name "Net-(U$1-SDA2{slash}RPI24{slash}RA8)") (class "Default")
      (node (ref "JP1") (pin "5") (pinfunction "5_5") (pintype "passive"))
      (node (ref "U$1") (pin "31") (pinfunction "SDA2/RPI24/RA8_31") (pintype "passive"))
    )
    (net (code "59") (name "Net-(U$1-VCAP)") (class "Default")
      (node (ref "C20") (pin "1") (pinfunction "1_1") (pintype "passive"))
      (node (ref "U$1") (pin "56") (pinfunction "VCAP_56") (pintype "passive"))
    )
    (net (code "60") (name "Net-(U$2-AVDD)") (class "Default")
      (node (ref "C19") (pin "2") (pinfunction "2_2") (pintype "passive"))
      (node (ref "U$2") (pin "27") (pinfunction "AVDD_27") (pintype "passive"))
    )
    (net (code "61") (name "Net-(U$2-BIAS)") (class "Default")
      (node (ref "R3") (pin "1") (pinfunction "1_1") (pintype "passive"))
      (node (ref "U$2") (pin "49") (pinfunction "BIAS_49") (pintype "passive"))
    )
    (net (code "62") (name "Net-(U$2-BST_A)") (class "Default")
      (node (ref "C9") (pin "1") (pinfunction "1_1") (pintype "passive"))
      (node (ref "U$2") (pin "48") (pinfunction "BST_A_48") (pintype "passive"))
    )
    (net (code "63") (name "Net-(U$2-BST_B)") (class "Default")
      (node (ref "C10") (pin "1") (pinfunction "1_1") (pintype "passive"))
      (node (ref "U$2") (pin "43") (pinfunction "BST_B_43") (pintype "passive"))
    )
    (net (code "64") (name "Net-(U$2-BST_BK)") (class "Default")
      (node (ref "C6") (pin "1") (pinfunction "1_1") (pintype "passive"))
      (node (ref "U$2") (pin "52") (pinfunction "BST_BK_52") (pintype "passive"))
    )
    (net (code "65") (name "Net-(U$2-BST_C)") (class "Default")
      (node (ref "C11") (pin "1") (pinfunction "1_1") (pintype "passive"))
      (node (ref "U$2") (pin "38") (pinfunction "BST_C_38") (pintype "passive"))
    )
    (net (code "66") (name "Net-(U$2-COMP)") (class "Default")
      (node (ref "C14") (pin "2") (pinfunction "2_2") (pintype "passive"))
      (node (ref "R9") (pin "1") (pinfunction "1_1") (pintype "passive"))
      (node (ref "U$2") (pin "2") (pinfunction "COMP_2") (pintype "passive"))
    )
    (net (code "67") (name "Net-(U$2-CP1)") (class "Default")
      (node (ref "C17") (pin "1") (pinfunction "1_1") (pintype "passive"))
      (node (ref "U$2") (pin "14") (pinfunction "CP1_14") (pintype "passive"))
    )
    (net (code "68") (name "Net-(U$2-CP2)") (class "Default")
      (node (ref "C17") (pin "2") (pinfunction "2_2") (pintype "passive"))
      (node (ref "U$2") (pin "15") (pinfunction "CP2_15") (pintype "passive"))
    )
    (net (code "69") (name "Net-(U$2-DVDD)") (class "Default")
      (node (ref "C18") (pin "2") (pinfunction "2_2") (pintype "passive"))
      (node (ref "R15") (pin "1") (pinfunction "1_1") (pintype "passive"))
      (node (ref "U$2") (pin "23") (pinfunction "DVDD_23") (pintype "passive"))
    )
    (net (code "70") (name "Net-(U$2-GVDD)") (class "Default")
      (node (ref "C16") (pin "1") (pinfunction "1_1") (pintype "passive"))
      (node (ref "U$2") (pin "13") (pinfunction "GVDD_13") (pintype "passive"))
    )
    (net (code "71") (name "Net-(U$2-OC_ADJ)") (class "Default")
      (node (ref "R15") (pin "2") (pinfunction "2_2") (pintype "passive"))
      (node (ref "R16") (pin "1") (pinfunction "1_1") (pintype "passive"))
      (node (ref "U$2") (pin "11") (pinfunction "OC_ADJ_11") (pintype "passive"))
    )
    (net (code "72") (name "Net-(U$2-RT_CLK)") (class "Default")
      (node (ref "R8") (pin "1") (pinfunction "1_1") (pintype "passive"))
      (node (ref "U$2") (pin "1") (pinfunction "RT_CLK_1") (pintype "passive"))
    )
    (net (code "73") (name "Net-(U$2-SS_TR)") (class "Default")
      (node (ref "C5") (pin "1") (pinfunction "1_1") (pintype "passive"))
      (node (ref "U$2") (pin "56") (pinfunction "SS_TR_56") (pintype "passive"))
    )
    (net (code "74") (name "Net-(U$2-VSENSE)") (class "Default")
      (node (ref "R10") (pin "1") (pinfunction "1_1") (pintype "passive"))
      (node (ref "R11") (pin "2") (pinfunction "2_2") (pintype "passive"))
      (node (ref "U$2") (pin "3") (pinfunction "VSENSE_3") (pintype "passive"))
    )
    (net (code "75") (name "Net-(U1-CPUMP+)") (class "Default")
      (node (ref "C29") (pin "1") (pinfunction "1_1") (pintype "passive"))
      (node (ref "U1") (pin "7") (pinfunction "CPUMP+_7") (pintype "passive"))
    )
    (net (code "76") (name "Net-(U1-CPUMP-)") (class "Default")
      (node (ref "C29") (pin "2") (pinfunction "2_2") (pintype "passive"))
      (node (ref "U1") (pin "6") (pinfunction "CPUMP-_6") (pintype "passive"))
    )
    (net (code "77") (name "OCTW") (class "Default")
      (node (ref "R13") (pin "1") (pinfunction "1_1") (pintype "passive"))
      (node (ref "U$1") (pin "53") (pinfunction "RD5_53") (pintype "passive"))
      (node (ref "U$2") (pin "5") (pinfunction "*OCTW_5") (pintype "passive"))
    )
    (net (code "78") (name "OUT_U") (class "Default")
      (node (ref "C9") (pin "2") (pinfunction "2_2") (pintype "passive"))
      (node (ref "JP7") (pin "3") (pinfunction "3_3") (pintype "passive"))
      (node (ref "U$2") (pin "46") (pinfunction "SH_A_46") (pintype "passive"))
      (node (ref "U$3") (pin "1") (pinfunction "S_1") (pintype "passive"))
      (node (ref "U$3") (pin "2") (pinfunction "S_2") (pintype "passive"))
      (node (ref "U$3") (pin "3") (pinfunction "S_3") (pintype "passive"))
      (node (ref "U$6") (pin "5") (pinfunction "D_5") (pintype "passive"))
      (node (ref "U$6") (pin "P$1") (pinfunction "D_P$1") (pintype "passive"))
      (node (ref "U$6") (pin "P$2") (pinfunction "D_P$2") (pintype "passive"))
      (node (ref "U$6") (pin "P$3") (pinfunction "D_P$3") (pintype "passive"))
      (node (ref "U$6") (pin "P$4") (pinfunction "D_P$4") (pintype "passive"))
      (node (ref "U$6") (pin "P$5") (pinfunction "D_P$5") (pintype "passive"))
      (node (ref "U$6") (pin "P$6") (pinfunction "D_P$6") (pintype "passive"))
      (node (ref "U$6") (pin "P$7") (pinfunction "D_P$7") (pintype "passive"))
      (node (ref "U$6") (pin "P$8") (pinfunction "D_P$8") (pintype "passive"))
      (node (ref "U$6") (pin "P$9") (pinfunction "D_P$9") (pintype "passive"))
    )
    (net (code "79") (name "OUT_V") (class "Default")
      (node (ref "C10") (pin "2") (pinfunction "2_2") (pintype "passive"))
      (node (ref "JP7") (pin "2") (pinfunction "2_2") (pintype "passive"))
      (node (ref "U$2") (pin "41") (pinfunction "SH_B_41") (pintype "passive"))
      (node (ref "U$4") (pin "1") (pinfunction "S_1") (pintype "passive"))
      (node (ref "U$4") (pin "2") (pinfunction "S_2") (pintype "passive"))
      (node (ref "U$4") (pin "3") (pinfunction "S_3") (pintype "passive"))
      (node (ref "U$7") (pin "5") (pinfunction "D_5") (pintype "passive"))
      (node (ref "U$7") (pin "P$1") (pinfunction "D_P$1") (pintype "passive"))
      (node (ref "U$7") (pin "P$2") (pinfunction "D_P$2") (pintype "passive"))
      (node (ref "U$7") (pin "P$3") (pinfunction "D_P$3") (pintype "passive"))
      (node (ref "U$7") (pin "P$4") (pinfunction "D_P$4") (pintype "passive"))
      (node (ref "U$7") (pin "P$5") (pinfunction "D_P$5") (pintype "passive"))
      (node (ref "U$7") (pin "P$6") (pinfunction "D_P$6") (pintype "passive"))
      (node (ref "U$7") (pin "P$7") (pinfunction "D_P$7") (pintype "passive"))
      (node (ref "U$7") (pin "P$8") (pinfunction "D_P$8") (pintype "passive"))
      (node (ref "U$7") (pin "P$9") (pinfunction "D_P$9") (pintype "passive"))
    )
    (net (code "80") (name "OUT_W") (class "Default")
      (node (ref "C11") (pin "2") (pinfunction "2_2") (pintype "passive"))
      (node (ref "JP7") (pin "1") (pinfunction "1_1") (pintype "passive"))
      (node (ref "U$2") (pin "36") (pinfunction "SH_C_36") (pintype "passive"))
      (node (ref "U$5") (pin "1") (pinfunction "S_1") (pintype "passive"))
      (node (ref "U$5") (pin "2") (pinfunction "S_2") (pintype "passive"))
      (node (ref "U$5") (pin "3") (pinfunction "S_3") (pintype "passive"))
      (node (ref "U$8") (pin "5") (pinfunction "D_5") (pintype "passive"))
      (node (ref "U$8") (pin "P$1") (pinfunction "D_P$1") (pintype "passive"))
      (node (ref "U$8") (pin "P$2") (pinfunction "D_P$2") (pintype "passive"))
      (node (ref "U$8") (pin "P$3") (pinfunction "D_P$3") (pintype "passive"))
      (node (ref "U$8") (pin "P$4") (pinfunction "D_P$4") (pintype "passive"))
      (node (ref "U$8") (pin "P$5") (pinfunction "D_P$5") (pintype "passive"))
      (node (ref "U$8") (pin "P$6") (pinfunction "D_P$6") (pintype "passive"))
      (node (ref "U$8") (pin "P$7") (pinfunction "D_P$7") (pintype "passive"))
      (node (ref "U$8") (pin "P$8") (pinfunction "D_P$8") (pintype "passive"))
      (node (ref "U$8") (pin "P$9") (pinfunction "D_P$9") (pintype "passive"))
    )
    (net (code "81") (name "PGC") (class "Default")
      (node (ref "JP3") (pin "5") (pinfunction "5_5") (pintype "passive"))
      (node (ref "U$1") (pin "44") (pinfunction "PGEC2/ASCL2/RP38/RB6_44") (pintype "passive"))
    )
    (net (code "82") (name "PGD") (class "Default")
      (node (ref "JP3") (pin "4") (pinfunction "4_4") (pintype "passive"))
      (node (ref "U$1") (pin "43") (pinfunction "PGED2/ASDA2/RP37/RB5_43") (pintype "passive"))
    )
    (net (code "83") (name "PVDD") (class "Default")
      (node (ref "C1") (pin "1") (pinfunction "1_1") (pintype "passive"))
      (node (ref "C2") (pin "1") (pinfunction "1_1") (pintype "passive"))
      (node (ref "C27") (pin "1") (pinfunction "+_1") (pintype "passive"))
      (node (ref "C3") (pin "1") (pinfunction "1_1") (pintype "passive"))
      (node (ref "C4") (pin "1") (pinfunction "1_1") (pintype "passive"))
      (node (ref "F1") (pin "A") (pinfunction "1_A") (pintype "passive"))
      (node (ref "J2") (pin "2") (pinfunction "1_2") (pintype "passive"))
      (node (ref "JP2") (pin "1") (pinfunction "1_1") (pintype "passive"))
      (node (ref "R18") (pin "1") (pinfunction "1_1") (pintype "passive"))
      (node (ref "R20") (pin "2") (pinfunction "2_2") (pintype "passive"))
      (node (ref "U$2") (pin "29") (pinfunction "PVDD1_29") (pintype "passive"))
      (node (ref "U$2") (pin "53") (pinfunction "PVDD2_53") (pintype "passive"))
      (node (ref "U$2") (pin "54") (pinfunction "PVDD2_2_54") (pintype "passive"))
      (node (ref "U$3") (pin "5") (pinfunction "D_5") (pintype "passive"))
      (node (ref "U$3") (pin "P$1") (pinfunction "D_P$1") (pintype "passive"))
      (node (ref "U$3") (pin "P$2") (pinfunction "D_P$2") (pintype "passive"))
      (node (ref "U$3") (pin "P$3") (pinfunction "D_P$3") (pintype "passive"))
      (node (ref "U$3") (pin "P$4") (pinfunction "D_P$4") (pintype "passive"))
      (node (ref "U$3") (pin "P$5") (pinfunction "D_P$5") (pintype "passive"))
      (node (ref "U$3") (pin "P$6") (pinfunction "D_P$6") (pintype "passive"))
      (node (ref "U$3") (pin "P$7") (pinfunction "D_P$7") (pintype "passive"))
      (node (ref "U$3") (pin "P$8") (pinfunction "D_P$8") (pintype "passive"))
      (node (ref "U$3") (pin "P$9") (pinfunction "D_P$9") (pintype "passive"))
      (node (ref "U$4") (pin "5") (pinfunction "D_5") (pintype "passive"))
      (node (ref "U$4") (pin "P$1") (pinfunction "D_P$1") (pintype "passive"))
      (node (ref "U$4") (pin "P$2") (pinfunction "D_P$2") (pintype "passive"))
      (node (ref "U$4") (pin "P$3") (pinfunction "D_P$3") (pintype "passive"))
      (node (ref "U$4") (pin "P$4") (pinfunction "D_P$4") (pintype "passive"))
      (node (ref "U$4") (pin "P$5") (pinfunction "D_P$5") (pintype "passive"))
      (node (ref "U$4") (pin "P$6") (pinfunction "D_P$6") (pintype "passive"))
      (node (ref "U$4") (pin "P$7") (pinfunction "D_P$7") (pintype "passive"))
      (node (ref "U$4") (pin "P$8") (pinfunction "D_P$8") (pintype "passive"))
      (node (ref "U$4") (pin "P$9") (pinfunction "D_P$9") (pintype "passive"))
      (node (ref "U$5") (pin "5") (pinfunction "D_5") (pintype "passive"))
      (node (ref "U$5") (pin "P$1") (pinfunction "D_P$1") (pintype "passive"))
      (node (ref "U$5") (pin "P$2") (pinfunction "D_P$2") (pintype "passive"))
      (node (ref "U$5") (pin "P$3") (pinfunction "D_P$3") (pintype "passive"))
      (node (ref "U$5") (pin "P$4") (pinfunction "D_P$4") (pintype "passive"))
      (node (ref "U$5") (pin "P$5") (pinfunction "D_P$5") (pintype "passive"))
      (node (ref "U$5") (pin "P$6") (pinfunction "D_P$6") (pintype "passive"))
      (node (ref "U$5") (pin "P$7") (pinfunction "D_P$7") (pintype "passive"))
      (node (ref "U$5") (pin "P$8") (pinfunction "D_P$8") (pintype "passive"))
      (node (ref "U$5") (pin "P$9") (pinfunction "D_P$9") (pintype "passive"))
    )
    (net (code "84") (name "PWM1") (class "Default")
      (node (ref "U$1") (pin "2") (pinfunction "RPI46/PWM1H/T3CK/RB14_2") (pintype "passive"))
      (node (ref "U$2") (pin "17") (pinfunction "INH_A_17") (pintype "passive"))
    )
    (net (code "85") (name "PWM3") (class "Default")
      (node (ref "U$1") (pin "62") (pinfunction "RPI44/PWM2H/RB12_62") (pintype "passive"))
      (node (ref "U$2") (pin "19") (pinfunction "INH_B_19") (pintype "passive"))
    )
    (net (code "86") (name "PWM5") (class "Default")
      (node (ref "U$1") (pin "60") (pinfunction "RP42/PWM3H/RB10_60") (pintype "passive"))
      (node (ref "U$2") (pin "21") (pinfunction "INH_C_21") (pintype "passive"))
    )
    (net (code "87") (name "PWRGD") (class "Default")
      (node (ref "R12") (pin "1") (pinfunction "1_1") (pintype "passive"))
      (node (ref "U$1") (pin "54") (pinfunction "RD6_54") (pintype "passive"))
      (node (ref "U$2") (pin "4") (pinfunction "PWRGD_4") (pintype "passive"))
    )
    (net (code "88") (name "RA11") (class "Default")
      (node (ref "JP5") (pin "3") (pinfunction "3_3") (pintype "passive"))
      (node (ref "U$1") (pin "12") (pinfunction "AN9/RPI27/RA11_12") (pintype "passive"))
    )
    (net (code "89") (name "RA12") (class "Default")
      (node (ref "JP5") (pin "2") (pinfunction "2_2") (pintype "passive"))
      (node (ref "U$1") (pin "11") (pinfunction "AN10/RPI28/RA12_11") (pintype "passive"))
    )
    (net (code "90") (name "SN1") (class "Default")
      (node (ref "C12") (pin "1") (pinfunction "1_1") (pintype "passive"))
      (node (ref "R7") (pin "2") (pinfunction "2_2") (pintype "passive"))
      (node (ref "U$2") (pin "33") (pinfunction "SN1_33") (pintype "passive"))
      (node (ref "U$2") (pin "44") (pinfunction "SL_A_44") (pintype "passive"))
      (node (ref "U$6") (pin "1") (pinfunction "S_1") (pintype "passive"))
      (node (ref "U$6") (pin "2") (pinfunction "S_2") (pintype "passive"))
      (node (ref "U$6") (pin "3") (pinfunction "S_3") (pintype "passive"))
    )
    (net (code "91") (name "SN2") (class "Default")
      (node (ref "C13") (pin "1") (pinfunction "1_1") (pintype "passive"))
      (node (ref "R4") (pin "2") (pinfunction "2_2") (pintype "passive"))
      (node (ref "U$2") (pin "31") (pinfunction "SN2_31") (pintype "passive"))
      (node (ref "U$2") (pin "34") (pinfunction "SL_C_34") (pintype "passive"))
      (node (ref "U$8") (pin "1") (pinfunction "S_1") (pintype "passive"))
      (node (ref "U$8") (pin "2") (pinfunction "S_2") (pintype "passive"))
      (node (ref "U$8") (pin "3") (pinfunction "S_3") (pintype "passive"))
    )
    (net (code "92") (name "VCC3V3") (class "Default")
      (node (ref "C21") (pin "1") (pinfunction "1_1") (pintype "passive"))
      (node (ref "C22") (pin "2") (pinfunction "2_2") (pintype "passive"))
      (node (ref "C23") (pin "2") (pinfunction "2_2") (pintype "passive"))
      (node (ref "C24") (pin "1") (pinfunction "1_1") (pintype "passive"))
      (node (ref "C25") (pin "1") (pinfunction "1_1") (pintype "passive"))
      (node (ref "C26") (pin "1") (pinfunction "1_1") (pintype "passive"))
      (node (ref "C31") (pin "1") (pinfunction "1_1") (pintype "passive"))
      (node (ref "C8") (pin "1") (pinfunction "1_1") (pintype "passive"))
      (node (ref "JP3") (pin "2") (pinfunction "2_2") (pintype "passive"))
      (node (ref "JP5") (pin "1") (pinfunction "1_1") (pintype "passive"))
      (node (ref "L1") (pin "P$2") (pinfunction "2_P$2") (pintype "passive"))
      (node (ref "R10") (pin "2") (pinfunction "2_2") (pintype "passive"))
      (node (ref "R12") (pin "2") (pinfunction "2_2") (pintype "passive"))
      (node (ref "R13") (pin "2") (pinfunction "2_2") (pintype "passive"))
      (node (ref "R14") (pin "2") (pinfunction "2_2") (pintype "passive"))
      (node (ref "R6") (pin "1") (pinfunction "1_1") (pintype "passive"))
      (node (ref "SJ1") (pin "1") (pinfunction "1_1") (pintype "passive"))
      (node (ref "SJ4") (pin "1") (pinfunction "1_1") (pintype "passive"))
      (node (ref "SJ5") (pin "1") (pinfunction "1_1") (pintype "passive"))
      (node (ref "SJ6") (pin "1") (pinfunction "1_1") (pintype "passive"))
      (node (ref "SJ7") (pin "1") (pinfunction "1_1") (pintype "passive"))
      (node (ref "U$1") (pin "10") (pinfunction "VDD_2_10") (pintype "passive"))
      (node (ref "U$1") (pin "19") (pinfunction "AVDD_19") (pintype "passive"))
      (node (ref "U$1") (pin "26") (pinfunction "VDD_3_26") (pintype "passive"))
      (node (ref "U$1") (pin "38") (pinfunction "VDD_4_38") (pintype "passive"))
      (node (ref "U$1") (pin "57") (pinfunction "VDD_57") (pintype "passive"))
      (node (ref "U$2") (pin "24") (pinfunction "REF_24") (pintype "passive"))
      (node (ref "U$2") (pin "8") (pinfunction "M_PWM_8") (pintype "passive"))
      (node (ref "U1") (pin "2") (pinfunction "ENABLE_2") (pintype "passive"))
      (node (ref "U1") (pin "3") (pinfunction "VIN_3") (pintype "passive"))
      (node (ref "U2") (pin "3") (pinfunction "VCC_3") (pintype "passive"))
      (node (ref "U3") (pin "13") (pinfunction "VCC_13") (pintype "passive"))
      (node (ref "U3") (pin "16") (pinfunction "EN_16") (pintype "passive"))
    )
    (net (code "93") (name "VCC5V") (class "Default")
      (node (ref "C30") (pin "2") (pinfunction "2_2") (pintype "passive"))
      (node (ref "JP5") (pin "6") (pinfunction "6_6") (pintype "passive"))
      (node (ref "U1") (pin "8") (pinfunction "VOUT_8") (pintype "passive"))
    )
    (net (code "94") (name "V_IN") (class "Default")
      (node (ref "F1") (pin "C") (pinfunction "2_C") (pintype "passive"))
      (node (ref "J1") (pin "2") (pinfunction "1_2") (pintype "passive"))
    )
    (net (code "95") (name "unconnected-(JP3-Pad6)") (class "Default")
      (node (ref "JP3") (pin "6") (pinfunction "6_6") (pintype "passive"))
    )
    (net (code "96") (name "unconnected-(U$1-AN11{slash}C1IN2-{slash}*U1CTS{slash}FLT4{slash}RC11-Pad24)") (class "Default")
      (node (ref "U$1") (pin "24") (pinfunction "AN11/C1IN2-/*U1CTS/FLT4/RC11_24") (pintype "passive"))
    )
    (net (code "97") (name "unconnected-(U$1-CVREF2O{slash}SDO1{slash}RP20{slash}T1CK{slash}RA4-Pad33)") (class "Default")
      (node (ref "U$1") (pin "33") (pinfunction "CVREF2O/SDO1/RP20/T1CK/RA4_33") (pintype "passive"))
    )
    (net (code "98") (name "unconnected-(U$1-OSC1{slash}CLKI{slash}RC12-Pad39)") (class "Default")
      (node (ref "U$1") (pin "39") (pinfunction "OSC1/CLKI/RC12_39") (pintype "passive"))
    )
    (net (code "99") (name "unconnected-(U$1-OSC2{slash}CLKO{slash}RC15-Pad40)") (class "Default")
      (node (ref "U$1") (pin "40") (pinfunction "OSC2/CLKO/RC15_40") (pintype "passive"))
    )
    (net (code "100") (name "unconnected-(U$1-RB43{slash}PWM3L{slash}RB11-Pad61)") (class "Default")
      (node (ref "U$1") (pin "61") (pinfunction "RB43/PWM3L/RB11_61") (pintype "passive"))
    )
    (net (code "101") (name "unconnected-(U$1-RD8-Pad42)") (class "Default")
      (node (ref "U$1") (pin "42") (pinfunction "RD8_42") (pintype "passive"))
    )
    (net (code "102") (name "unconnected-(U$1-RP57{slash}RC9-Pad55)") (class "Default")
      (node (ref "U$1") (pin "55") (pinfunction "RP57/RC9_55") (pintype "passive"))
    )
    (net (code "103") (name "unconnected-(U$1-RPI45{slash}PWM2L{slash}CTPLS{slash}RB13-Pad63)") (class "Default")
      (node (ref "U$1") (pin "63") (pinfunction "RPI45/PWM2L/CTPLS/RB13_63") (pintype "passive"))
    )
    (net (code "104") (name "unconnected-(U$1-SCL1{slash}RPI53{slash}RC5-Pad37)") (class "Default")
      (node (ref "U$1") (pin "37") (pinfunction "SCL1/RPI53/RC5_37") (pintype "passive"))
    )
    (net (code "105") (name "unconnected-(U$1-TDI{slash}RA7-Pad1)") (class "Default")
      (node (ref "U$1") (pin "1") (pinfunction "TDI/RA7_1") (pintype "passive"))
    )
    (net (code "106") (name "unconnected-(U$1-TDO{slash}RA10-Pad64)") (class "Default")
      (node (ref "U$1") (pin "64") (pinfunction "TDO/RA10_64") (pintype "passive"))
    )
    (net (code "107") (name "unconnected-(U$2-EN_BUCK-Pad55)") (class "Default")
      (node (ref "U$2") (pin "55") (pinfunction "EN_BUCK_55") (pintype "passive"))
    )
    (net (code "108") (name "unconnected-(U$2-INL_A-Pad18)") (class "Default")
      (node (ref "U$2") (pin "18") (pinfunction "INL_A_18") (pintype "passive"))
    )
    (net (code "109") (name "unconnected-(U$2-INL_B-Pad20)") (class "Default")
      (node (ref "U$2") (pin "20") (pinfunction "INL_B_20") (pintype "passive"))
    )
    (net (code "110") (name "unconnected-(U$2-INL_C-Pad22)") (class "Default")
      (node (ref "U$2") (pin "22") (pinfunction "INL_C_22") (pintype "passive"))
    )
    (net (code "111") (name "unconnected-(U$2-PH_2-Pad50)") (class "Default")
      (node (ref "U$2") (pin "50") (pinfunction "PH_2_50") (pintype "passive"))
    )
    (net (code "112") (name "unconnected-(U1-NC-Pad1)") (class "Default")
      (node (ref "U1") (pin "1") (pinfunction "NC_1") (pintype "passive"))
    )
    (net (code "113") (name "unconnected-(U2-NC-Pad8)") (class "Default")
      (node (ref "U2") (pin "8") (pinfunction "NC_8") (pintype "passive"))
    )
    (net (code "114") (name "unconnected-(U2-NC_2-Pad5)") (class "Default")
      (node (ref "U2") (pin "5") (pinfunction "NC_2_5") (pintype "passive"))
    )
    (net (code "115") (name "unconnected-(U3-RIN4+-Pad7)") (class "Default")
      (node (ref "U3") (pin "7") (pinfunction "RIN4+_7") (pintype "passive"))
    )
    (net (code "116") (name "unconnected-(U3-RIN4-Pad8)") (class "Default")
      (node (ref "U3") (pin "8") (pinfunction "RIN4_8") (pintype "passive"))
    )
    (net (code "117") (name "unconnected-(U3-ROUT4-Pad10)") (class "Default")
      (node (ref "U3") (pin "10") (pinfunction "ROUT4_10") (pintype "passive"))
    )
  )
)
